# PT_2016_PB_4lyr_Rev2.net
KiCad netlist of a schematic drawn in EAGLE
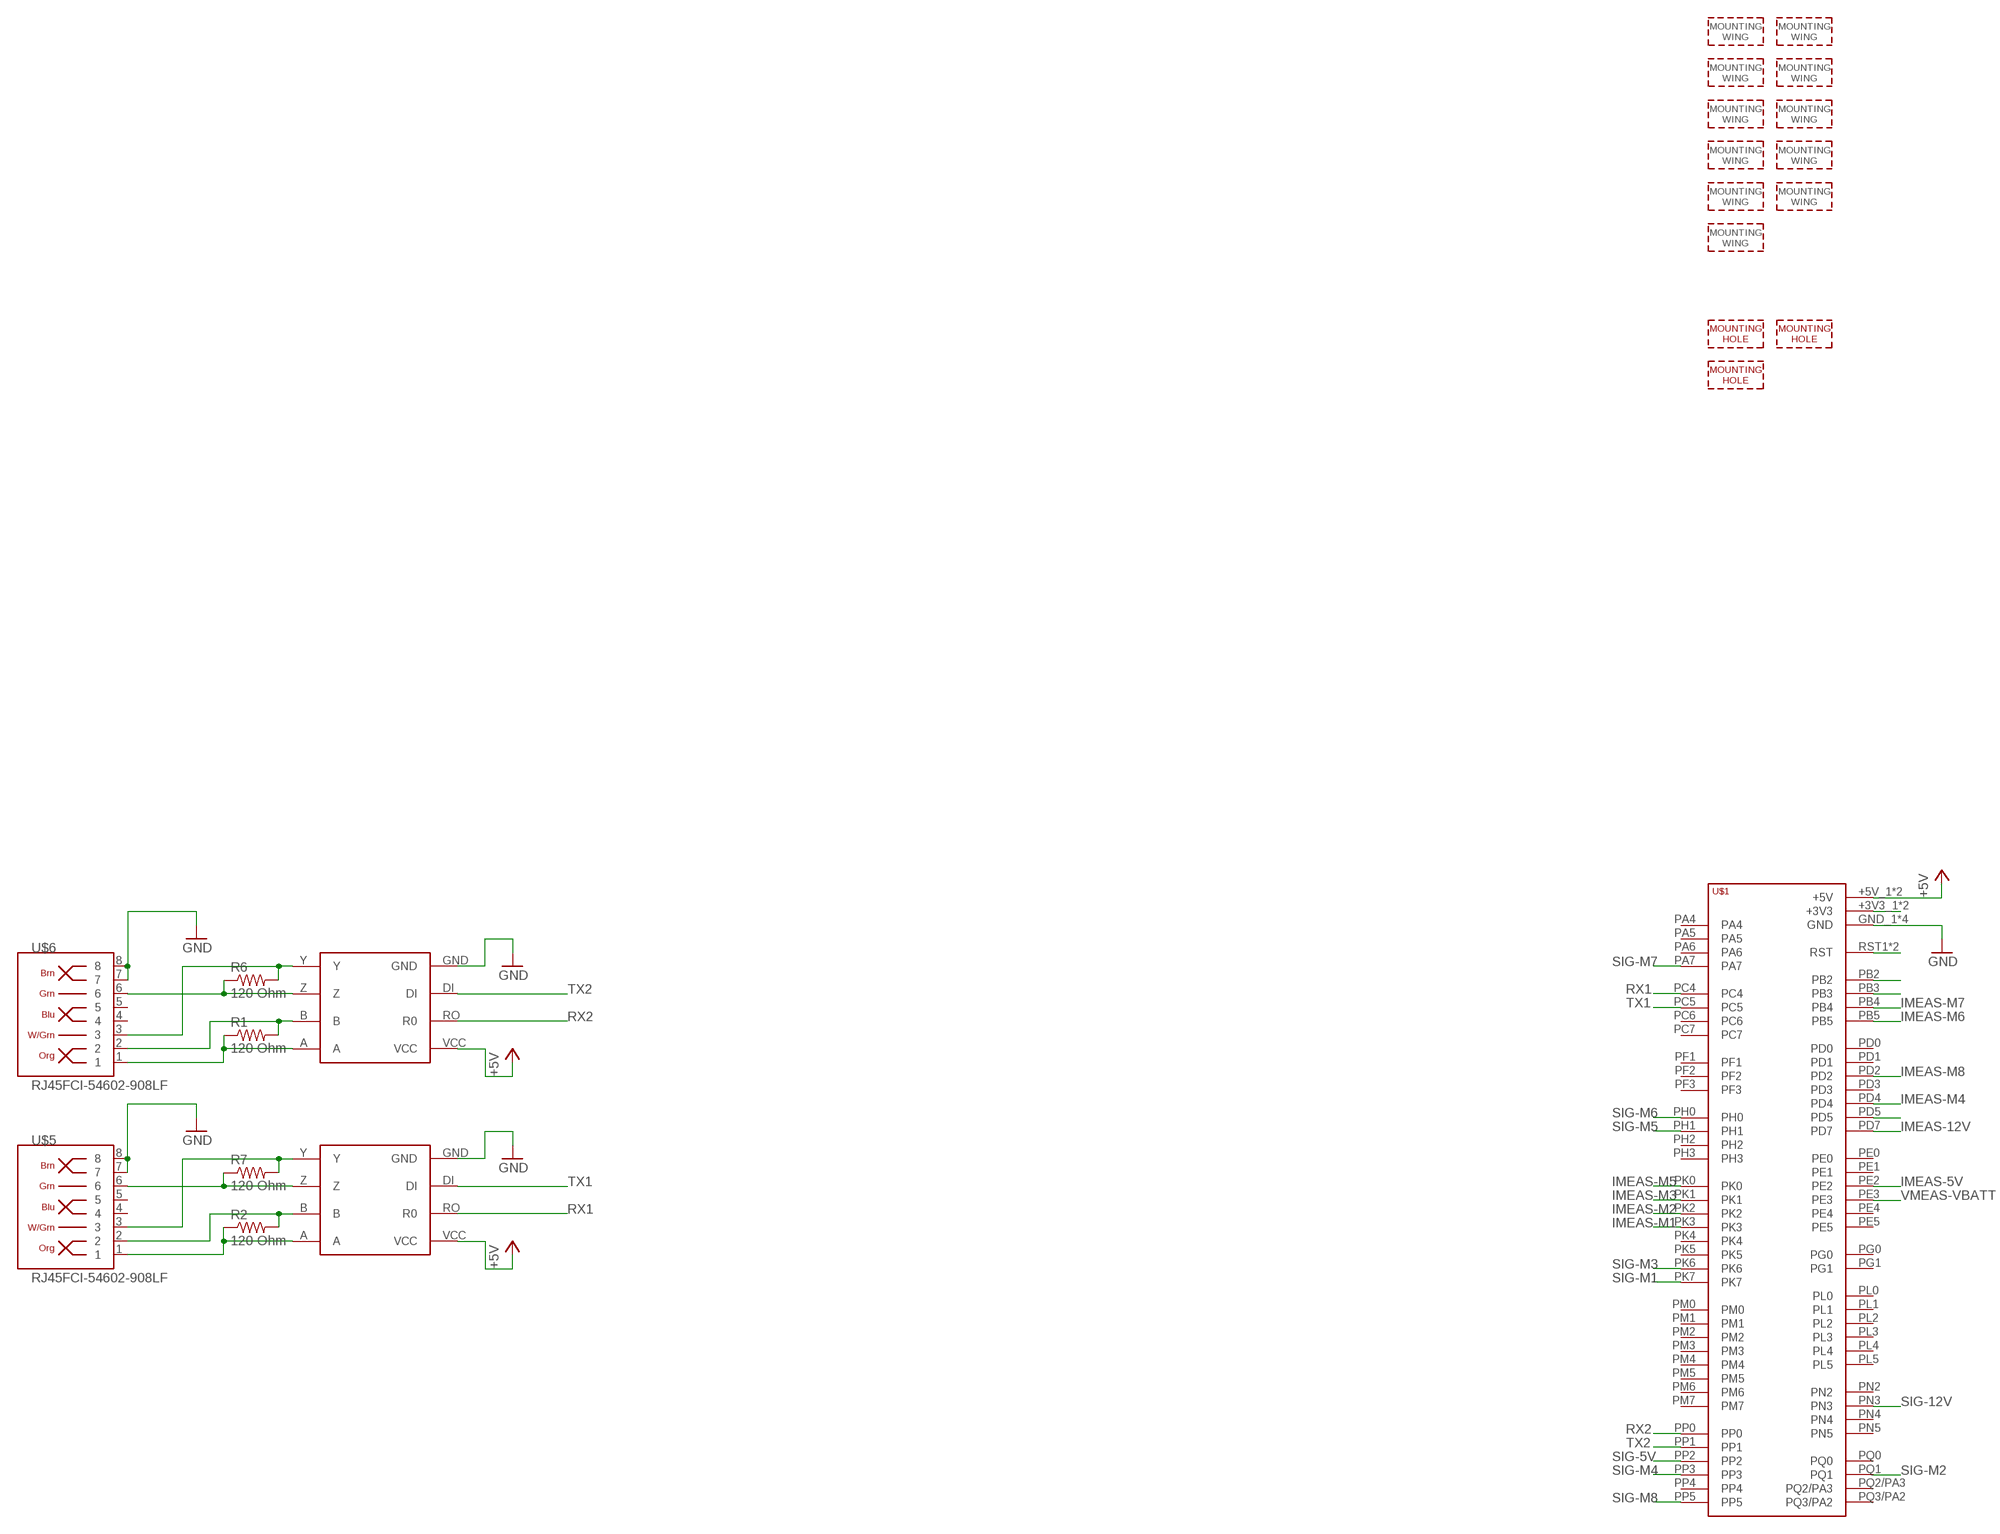
[diagram p0: schematic, sheet 1, part 1 of 3]
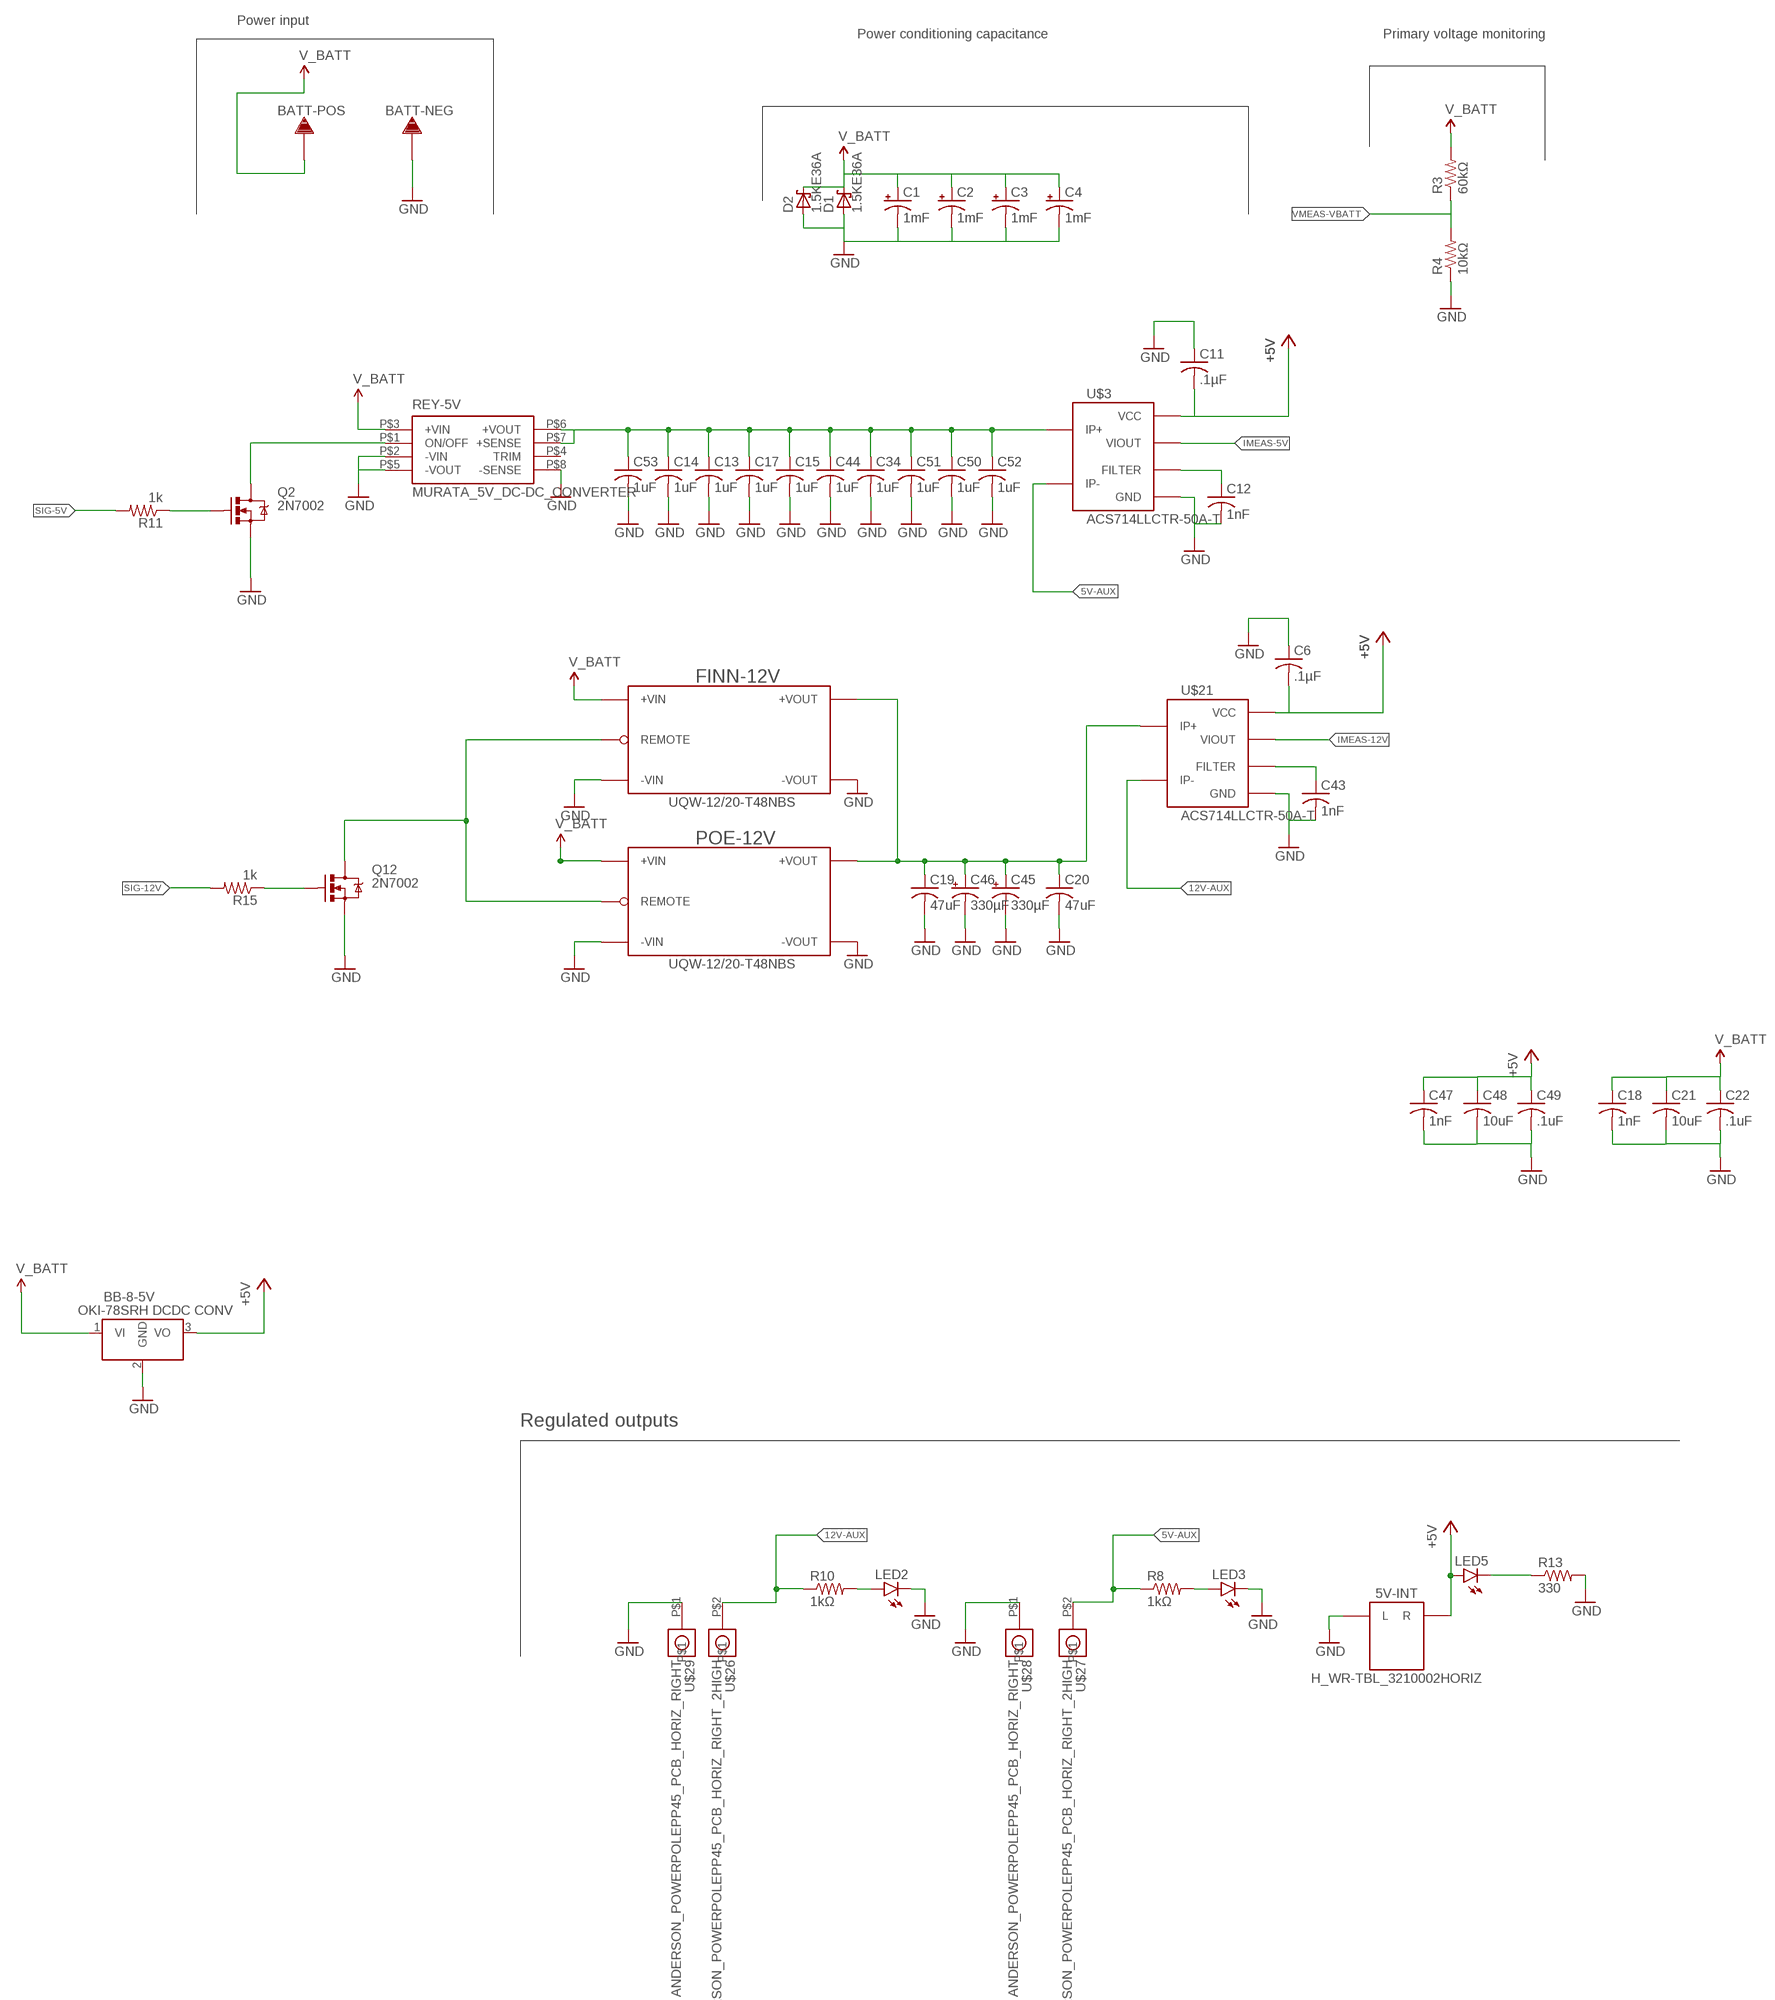
[diagram p1: schematic, sheet 1, part 2 of 3]
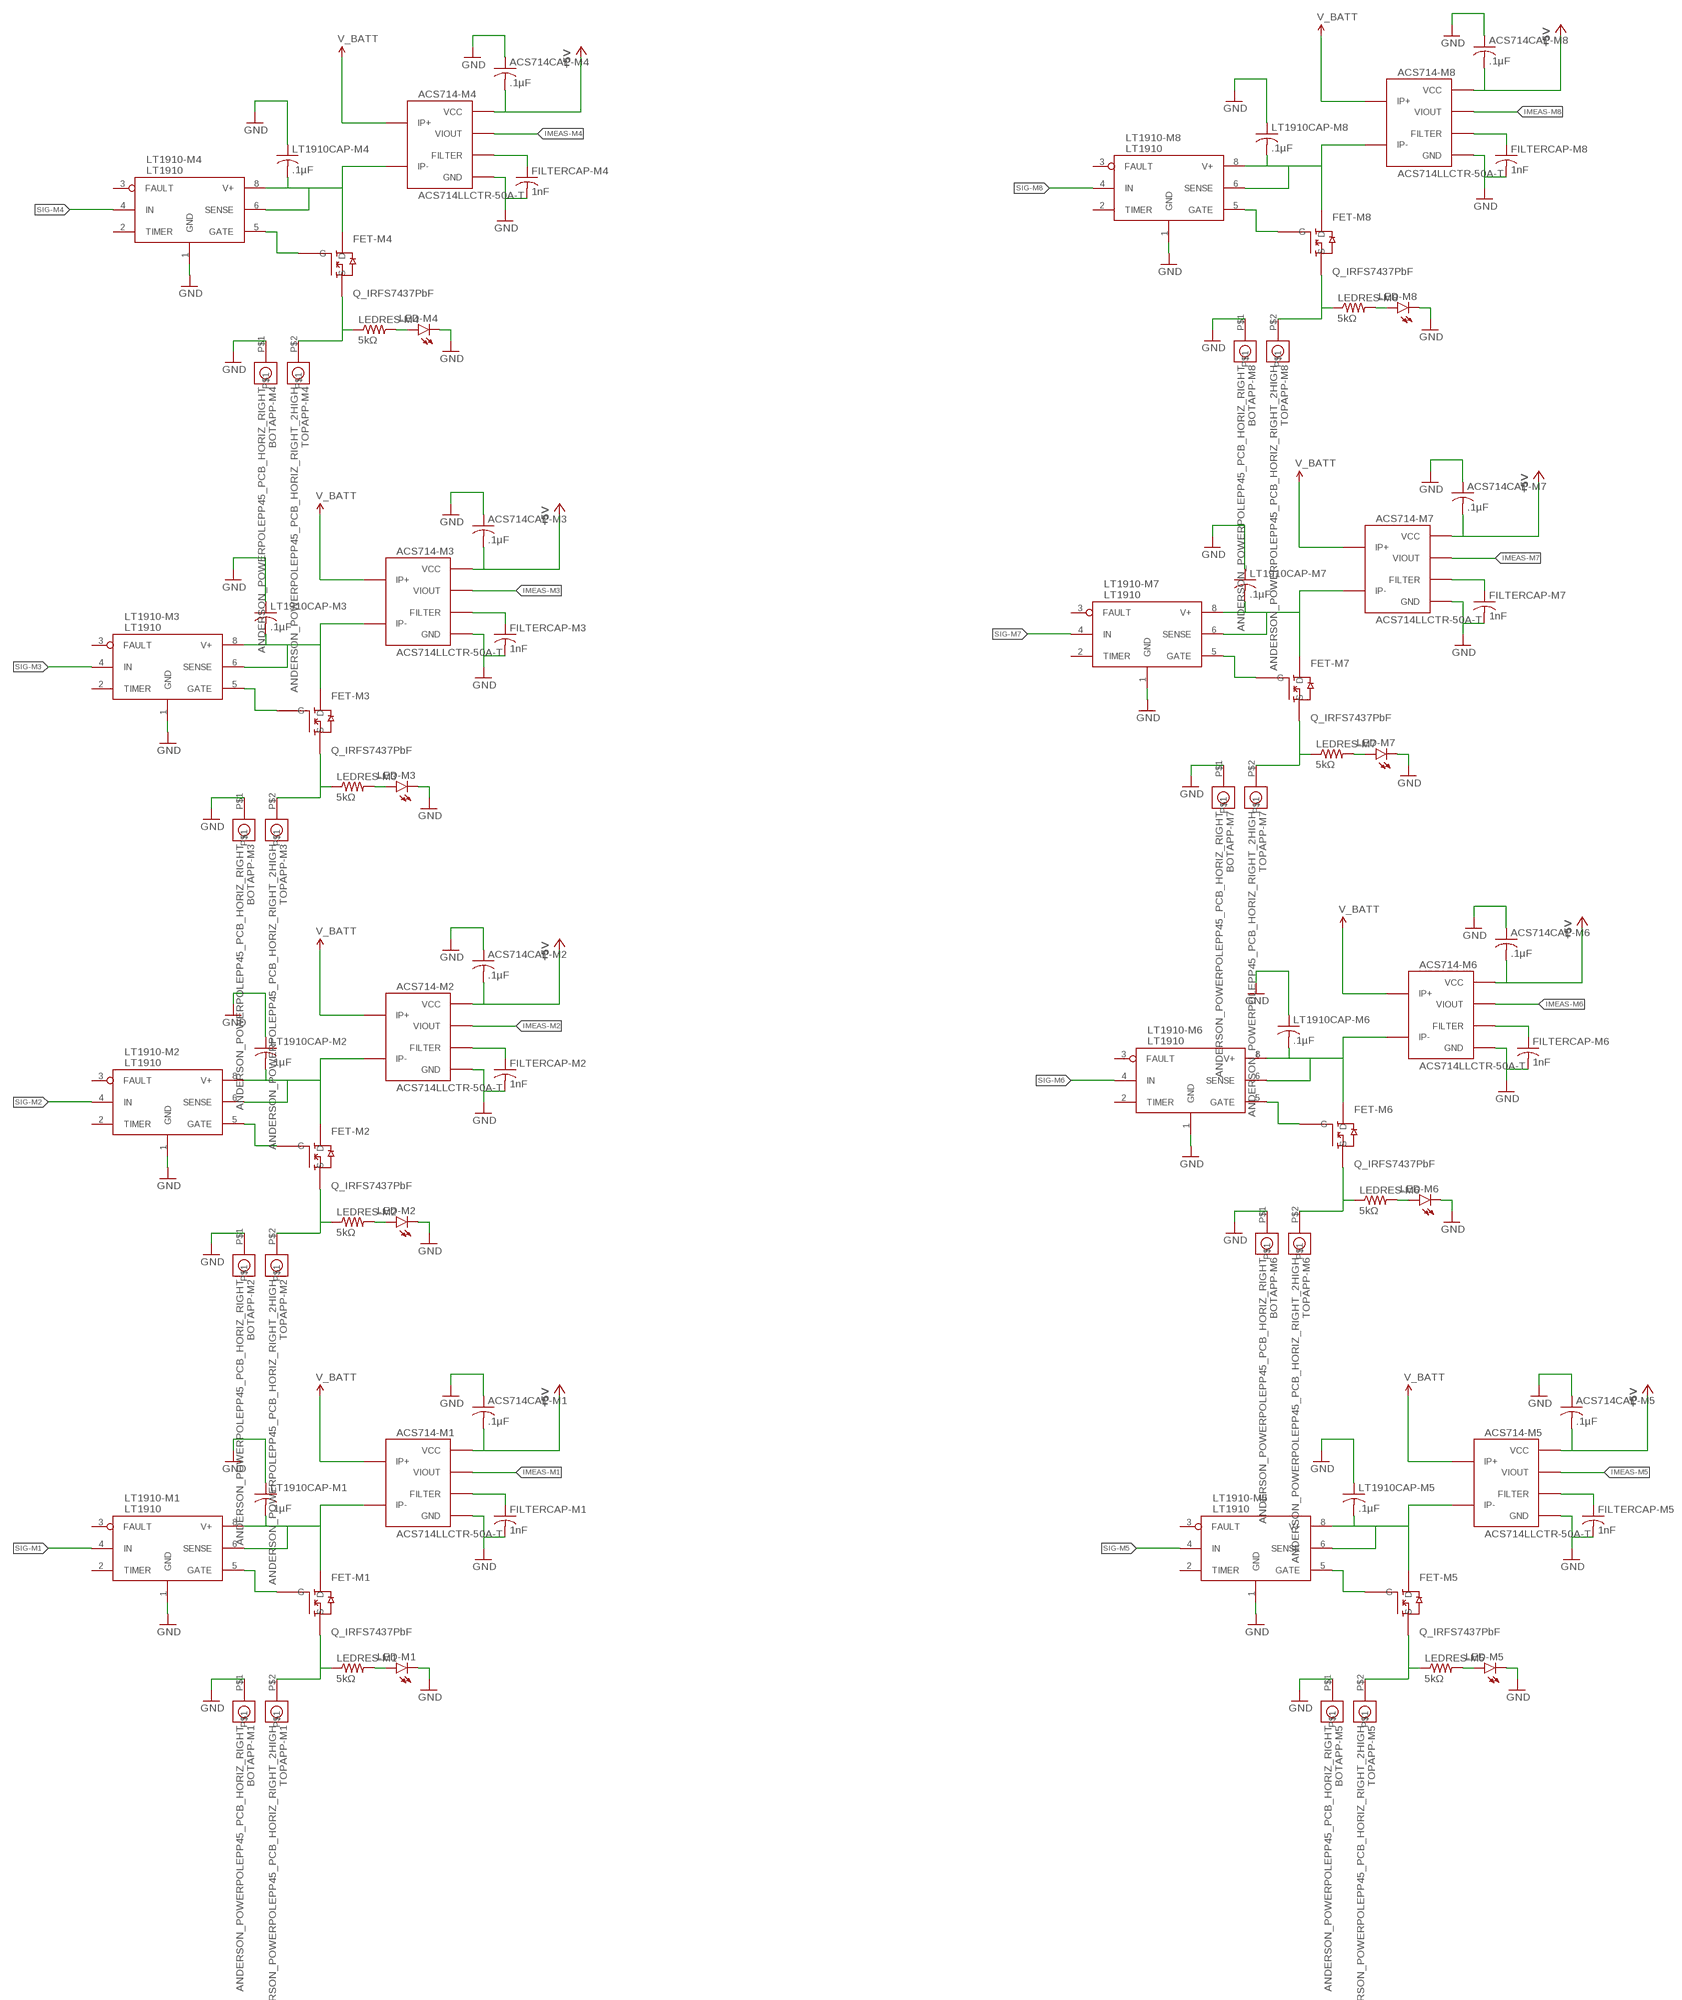
[diagram p2: schematic, sheet 1, part 3 of 3]

(export (version "E")
  (design (tool "Eeschema 10.0.6"))
  (components
    (comp (ref "5V-INT")
      (value "H_WR-TBL_3210002HORIZ")
      (footprint "eagle-import:691322110002")
      (libsource (lib "eagle-import") (part "H_WR-TBL_3210002HORIZ"))
    )
    (comp (ref "ACS714-M1")
      (value "ACS714LLCTR-50A-T")
      (footprint "eagle-import:SOIC8_ACS711")
      (libsource (lib "eagle-import") (part "Q_ACS714"))
    )
    (comp (ref "ACS714-M2")
      (value "ACS714LLCTR-50A-T")
      (footprint "eagle-import:SOIC8_ACS711")
      (libsource (lib "eagle-import") (part "Q_ACS714"))
    )
    (comp (ref "ACS714-M3")
      (value "ACS714LLCTR-50A-T")
      (footprint "eagle-import:SOIC8_ACS711")
      (libsource (lib "eagle-import") (part "Q_ACS714"))
    )
    (comp (ref "ACS714-M4")
      (value "ACS714LLCTR-50A-T")
      (footprint "eagle-import:SOIC8_ACS711")
      (libsource (lib "eagle-import") (part "Q_ACS714"))
    )
    (comp (ref "ACS714-M5")
      (value "ACS714LLCTR-50A-T")
      (footprint "eagle-import:SOIC8_ACS711")
      (libsource (lib "eagle-import") (part "Q_ACS714"))
    )
    (comp (ref "ACS714-M6")
      (value "ACS714LLCTR-50A-T")
      (footprint "eagle-import:SOIC8_ACS711")
      (libsource (lib "eagle-import") (part "Q_ACS714"))
    )
    (comp (ref "ACS714-M7")
      (value "ACS714LLCTR-50A-T")
      (footprint "eagle-import:SOIC8_ACS711")
      (libsource (lib "eagle-import") (part "Q_ACS714"))
    )
    (comp (ref "ACS714-M8")
      (value "ACS714LLCTR-50A-T")
      (footprint "eagle-import:SOIC8_ACS711")
      (libsource (lib "eagle-import") (part "Q_ACS714"))
    )
    (comp (ref "ACS714CAP-M1")
      (value ".1µF")
      (footprint "eagle-import:C1206")
      (libsource (lib "eagle-import") (part "C-USC1206"))
    )
    (comp (ref "ACS714CAP-M2")
      (value ".1µF")
      (footprint "eagle-import:C1206")
      (libsource (lib "eagle-import") (part "C-USC1206"))
    )
    (comp (ref "ACS714CAP-M3")
      (value ".1µF")
      (footprint "eagle-import:C1206")
      (libsource (lib "eagle-import") (part "C-USC1206"))
    )
    (comp (ref "ACS714CAP-M4")
      (value ".1µF")
      (footprint "eagle-import:C1206")
      (libsource (lib "eagle-import") (part "C-USC1206"))
    )
    (comp (ref "ACS714CAP-M5")
      (value ".1µF")
      (footprint "eagle-import:C1206")
      (libsource (lib "eagle-import") (part "C-USC1206"))
    )
    (comp (ref "ACS714CAP-M6")
      (value ".1µF")
      (footprint "eagle-import:C1206")
      (libsource (lib "eagle-import") (part "C-USC1206"))
    )
    (comp (ref "ACS714CAP-M7")
      (value ".1µF")
      (footprint "eagle-import:C1206")
      (libsource (lib "eagle-import") (part "C-USC1206"))
    )
    (comp (ref "ACS714CAP-M8")
      (value ".1µF")
      (footprint "eagle-import:C1206")
      (libsource (lib "eagle-import") (part "C-USC1206"))
    )
    (comp (ref "BATT-NEG")
      (value "TERMINAL_HOLE")
      (footprint "eagle-import:LARGE_TERMINAL_HOLE")
      (libsource (lib "eagle-import") (part "TERMINAL_HOLE"))
    )
    (comp (ref "BATT-POS")
      (value "TERMINAL_HOLE")
      (footprint "eagle-import:LARGE_TERMINAL_HOLE")
      (libsource (lib "eagle-import") (part "TERMINAL_HOLE"))
    )
    (comp (ref "BB-8-5V")
      (value "Q_OKI-78SR")
      (footprint "eagle-import:OKI-78SRH")
      (libsource (lib "eagle-import") (part "Q_OKI-78SR"))
    )
    (comp (ref "BOTAPP-M1")
      (value "ANDERSON_POWERPOLEPP45_PCB_HORIZ_RIGHT")
      (footprint "eagle-import:APP45_PCB_HORIZ_RIGHT")
      (libsource (lib "eagle-import") (part "ANDERSON_POWERPOLEPP45_PCB_HORIZ_RIGHT"))
    )
    (comp (ref "BOTAPP-M2")
      (value "ANDERSON_POWERPOLEPP45_PCB_HORIZ_RIGHT")
      (footprint "eagle-import:APP45_PCB_HORIZ_RIGHT")
      (libsource (lib "eagle-import") (part "ANDERSON_POWERPOLEPP45_PCB_HORIZ_RIGHT"))
    )
    (comp (ref "BOTAPP-M3")
      (value "ANDERSON_POWERPOLEPP45_PCB_HORIZ_RIGHT")
      (footprint "eagle-import:APP45_PCB_HORIZ_RIGHT")
      (libsource (lib "eagle-import") (part "ANDERSON_POWERPOLEPP45_PCB_HORIZ_RIGHT"))
    )
    (comp (ref "BOTAPP-M4")
      (value "ANDERSON_POWERPOLEPP45_PCB_HORIZ_RIGHT")
      (footprint "eagle-import:APP45_PCB_HORIZ_RIGHT")
      (libsource (lib "eagle-import") (part "ANDERSON_POWERPOLEPP45_PCB_HORIZ_RIGHT"))
    )
    (comp (ref "BOTAPP-M5")
      (value "ANDERSON_POWERPOLEPP45_PCB_HORIZ_RIGHT")
      (footprint "eagle-import:APP45_PCB_HORIZ_RIGHT")
      (libsource (lib "eagle-import") (part "ANDERSON_POWERPOLEPP45_PCB_HORIZ_RIGHT"))
    )
    (comp (ref "BOTAPP-M6")
      (value "ANDERSON_POWERPOLEPP45_PCB_HORIZ_RIGHT")
      (footprint "eagle-import:APP45_PCB_HORIZ_RIGHT")
      (libsource (lib "eagle-import") (part "ANDERSON_POWERPOLEPP45_PCB_HORIZ_RIGHT"))
    )
    (comp (ref "BOTAPP-M7")
      (value "ANDERSON_POWERPOLEPP45_PCB_HORIZ_RIGHT")
      (footprint "eagle-import:APP45_PCB_HORIZ_RIGHT")
      (libsource (lib "eagle-import") (part "ANDERSON_POWERPOLEPP45_PCB_HORIZ_RIGHT"))
    )
    (comp (ref "BOTAPP-M8")
      (value "ANDERSON_POWERPOLEPP45_PCB_HORIZ_RIGHT")
      (footprint "eagle-import:APP45_PCB_HORIZ_RIGHT")
      (libsource (lib "eagle-import") (part "ANDERSON_POWERPOLEPP45_PCB_HORIZ_RIGHT"))
    )
    (comp (ref "C1")
      (value "1mF")
      (footprint "eagle-import:C_12.5MM")
      (libsource (lib "eagle-import") (part "C_POL12.5MM_NORMAL"))
    )
    (comp (ref "C2")
      (value "1mF")
      (footprint "eagle-import:C_12.5MM")
      (libsource (lib "eagle-import") (part "C_POL12.5MM_NORMAL"))
    )
    (comp (ref "C3")
      (value "1mF")
      (footprint "eagle-import:C_12.5MM")
      (libsource (lib "eagle-import") (part "C_POL12.5MM_NORMAL"))
    )
    (comp (ref "C4")
      (value "1mF")
      (footprint "eagle-import:C_12.5MM")
      (libsource (lib "eagle-import") (part "C_POL12.5MM_NORMAL"))
    )
    (comp (ref "C6")
      (value ".1µF")
      (footprint "eagle-import:C1206")
      (libsource (lib "eagle-import") (part "C-USC1206"))
    )
    (comp (ref "C11")
      (value ".1µF")
      (footprint "eagle-import:C1206")
      (libsource (lib "eagle-import") (part "C-USC1206"))
    )
    (comp (ref "C12")
      (value "1nF")
      (footprint "eagle-import:C1206")
      (libsource (lib "eagle-import") (part "C-USC1206"))
    )
    (comp (ref "C13")
      (value "1uF")
      (footprint "eagle-import:C1206")
      (libsource (lib "eagle-import") (part "C-USC1206"))
    )
    (comp (ref "C14")
      (value "1uF")
      (footprint "eagle-import:C1206")
      (libsource (lib "eagle-import") (part "C-USC1206"))
    )
    (comp (ref "C15")
      (value "1uF")
      (footprint "eagle-import:C1206")
      (libsource (lib "eagle-import") (part "C-USC1206"))
    )
    (comp (ref "C17")
      (value "1uF")
      (footprint "eagle-import:C1206")
      (libsource (lib "eagle-import") (part "C-USC1206"))
    )
    (comp (ref "C18")
      (value "1nF")
      (footprint "eagle-import:C1206")
      (libsource (lib "eagle-import") (part "C-USC1206"))
    )
    (comp (ref "C19")
      (value "47uF")
      (footprint "eagle-import:C1206")
      (libsource (lib "eagle-import") (part "C-USC1206"))
    )
    (comp (ref "C20")
      (value "47uF")
      (footprint "eagle-import:C1206")
      (libsource (lib "eagle-import") (part "C-USC1206"))
    )
    (comp (ref "C21")
      (value "10uF")
      (footprint "eagle-import:C1206")
      (libsource (lib "eagle-import") (part "C-USC1206"))
    )
    (comp (ref "C22")
      (value ".1uF")
      (footprint "eagle-import:C1206")
      (libsource (lib "eagle-import") (part "C-USC1206"))
    )
    (comp (ref "C34")
      (value "1uF")
      (footprint "eagle-import:C1206")
      (libsource (lib "eagle-import") (part "C-USC1206"))
    )
    (comp (ref "C43")
      (value "1nF")
      (footprint "eagle-import:C1206")
      (libsource (lib "eagle-import") (part "C-USC1206"))
    )
    (comp (ref "C44")
      (value "1uF")
      (footprint "eagle-import:C1206")
      (libsource (lib "eagle-import") (part "C-USC1206"))
    )
    (comp (ref "C45")
      (value "330µF")
      (footprint "eagle-import:E5-8,5")
      (libsource (lib "eagle-import") (part "CPOL-USE5-8.5"))
    )
    (comp (ref "C46")
      (value "330µF")
      (footprint "eagle-import:E5-8,5")
      (libsource (lib "eagle-import") (part "CPOL-USE5-8.5"))
    )
    (comp (ref "C47")
      (value "1nF")
      (footprint "eagle-import:C1206")
      (libsource (lib "eagle-import") (part "C-USC1206"))
    )
    (comp (ref "C48")
      (value "10uF")
      (footprint "eagle-import:C1206")
      (libsource (lib "eagle-import") (part "C-USC1206"))
    )
    (comp (ref "C49")
      (value ".1uF")
      (footprint "eagle-import:C1206")
      (libsource (lib "eagle-import") (part "C-USC1206"))
    )
    (comp (ref "C50")
      (value "1uF")
      (footprint "eagle-import:C1206")
      (libsource (lib "eagle-import") (part "C-USC1206"))
    )
    (comp (ref "C51")
      (value "1uF")
      (footprint "eagle-import:C1206")
      (libsource (lib "eagle-import") (part "C-USC1206"))
    )
    (comp (ref "C52")
      (value "1uF")
      (footprint "eagle-import:C1206")
      (libsource (lib "eagle-import") (part "C-USC1206"))
    )
    (comp (ref "C53")
      (value "1uF")
      (footprint "eagle-import:C1206")
      (libsource (lib "eagle-import") (part "C-USC1206"))
    )
    (comp (ref "D1")
      (value "1.5KE36A")
      (footprint "eagle-import:CB429-17")
      (libsource (lib "eagle-import") (part "15KEXX"))
    )
    (comp (ref "D2")
      (value "1.5KE36A")
      (footprint "eagle-import:CB429-17")
      (libsource (lib "eagle-import") (part "15KEXX"))
    )
    (comp (ref "FET-M1")
      (value "Q_IRFS7437PbF")
      (footprint "eagle-import:D2PACK")
      (libsource (lib "eagle-import") (part "Q_IRF7437SMD"))
    )
    (comp (ref "FET-M2")
      (value "Q_IRFS7437PbF")
      (footprint "eagle-import:D2PACK")
      (libsource (lib "eagle-import") (part "Q_IRF7437SMD"))
    )
    (comp (ref "FET-M3")
      (value "Q_IRFS7437PbF")
      (footprint "eagle-import:D2PACK")
      (libsource (lib "eagle-import") (part "Q_IRF7437SMD"))
    )
    (comp (ref "FET-M4")
      (value "Q_IRFS7437PbF")
      (footprint "eagle-import:D2PACK")
      (libsource (lib "eagle-import") (part "Q_IRF7437SMD"))
    )
    (comp (ref "FET-M5")
      (value "Q_IRFS7437PbF")
      (footprint "eagle-import:D2PACK")
      (libsource (lib "eagle-import") (part "Q_IRF7437SMD"))
    )
    (comp (ref "FET-M6")
      (value "Q_IRFS7437PbF")
      (footprint "eagle-import:D2PACK")
      (libsource (lib "eagle-import") (part "Q_IRF7437SMD"))
    )
    (comp (ref "FET-M7")
      (value "Q_IRFS7437PbF")
      (footprint "eagle-import:D2PACK")
      (libsource (lib "eagle-import") (part "Q_IRF7437SMD"))
    )
    (comp (ref "FET-M8")
      (value "Q_IRFS7437PbF")
      (footprint "eagle-import:D2PACK")
      (libsource (lib "eagle-import") (part "Q_IRF7437SMD"))
    )
    (comp (ref "FILTERCAP-M1")
      (value "1nF")
      (footprint "eagle-import:C1206")
      (libsource (lib "eagle-import") (part "C-USC1206"))
    )
    (comp (ref "FILTERCAP-M2")
      (value "1nF")
      (footprint "eagle-import:C1206")
      (libsource (lib "eagle-import") (part "C-USC1206"))
    )
    (comp (ref "FILTERCAP-M3")
      (value "1nF")
      (footprint "eagle-import:C1206")
      (libsource (lib "eagle-import") (part "C-USC1206"))
    )
    (comp (ref "FILTERCAP-M4")
      (value "1nF")
      (footprint "eagle-import:C1206")
      (libsource (lib "eagle-import") (part "C-USC1206"))
    )
    (comp (ref "FILTERCAP-M5")
      (value "1nF")
      (footprint "eagle-import:C1206")
      (libsource (lib "eagle-import") (part "C-USC1206"))
    )
    (comp (ref "FILTERCAP-M6")
      (value "1nF")
      (footprint "eagle-import:C1206")
      (libsource (lib "eagle-import") (part "C-USC1206"))
    )
    (comp (ref "FILTERCAP-M7")
      (value "1nF")
      (footprint "eagle-import:C1206")
      (libsource (lib "eagle-import") (part "C-USC1206"))
    )
    (comp (ref "FILTERCAP-M8")
      (value "1nF")
      (footprint "eagle-import:C1206")
      (libsource (lib "eagle-import") (part "C-USC1206"))
    )
    (comp (ref "FINN-12V")
      (value "UQW-12/20-T48NBS")
      (footprint "eagle-import:U-T48-QB-NO_TRIM")
      (libsource (lib "eagle-import") (part "UQW-12/20-T48NBS"))
    )
    (comp (ref "LED-M1")
      (value "LED1206")
      (footprint "eagle-import:LED-1206")
      (libsource (lib "eagle-import") (part "LED1206"))
    )
    (comp (ref "LED-M2")
      (value "LED1206")
      (footprint "eagle-import:LED-1206")
      (libsource (lib "eagle-import") (part "LED1206"))
    )
    (comp (ref "LED-M3")
      (value "LED1206")
      (footprint "eagle-import:LED-1206")
      (libsource (lib "eagle-import") (part "LED1206"))
    )
    (comp (ref "LED-M4")
      (value "LED1206")
      (footprint "eagle-import:LED-1206")
      (libsource (lib "eagle-import") (part "LED1206"))
    )
    (comp (ref "LED-M5")
      (value "LED1206")
      (footprint "eagle-import:LED-1206")
      (libsource (lib "eagle-import") (part "LED1206"))
    )
    (comp (ref "LED-M6")
      (value "LED1206")
      (footprint "eagle-import:LED-1206")
      (libsource (lib "eagle-import") (part "LED1206"))
    )
    (comp (ref "LED-M7")
      (value "LED1206")
      (footprint "eagle-import:LED-1206")
      (libsource (lib "eagle-import") (part "LED1206"))
    )
    (comp (ref "LED-M8")
      (value "LED1206")
      (footprint "eagle-import:LED-1206")
      (libsource (lib "eagle-import") (part "LED1206"))
    )
    (comp (ref "LED2")
      (value "LED1206")
      (footprint "eagle-import:LED-1206")
      (libsource (lib "eagle-import") (part "LED1206"))
    )
    (comp (ref "LED3")
      (value "LED1206")
      (footprint "eagle-import:LED-1206")
      (libsource (lib "eagle-import") (part "LED1206"))
    )
    (comp (ref "LED5")
      (value "LED1206")
      (footprint "eagle-import:LED-1206")
      (libsource (lib "eagle-import") (part "LED1206"))
    )
    (comp (ref "LEDRES-M1")
      (value "5kΩ")
      (footprint "eagle-import:1206")
      (libsource (lib "eagle-import") (part "RESISTOR1206"))
    )
    (comp (ref "LEDRES-M2")
      (value "5kΩ")
      (footprint "eagle-import:1206")
      (libsource (lib "eagle-import") (part "RESISTOR1206"))
    )
    (comp (ref "LEDRES-M3")
      (value "5kΩ")
      (footprint "eagle-import:1206")
      (libsource (lib "eagle-import") (part "RESISTOR1206"))
    )
    (comp (ref "LEDRES-M4")
      (value "5kΩ")
      (footprint "eagle-import:1206")
      (libsource (lib "eagle-import") (part "RESISTOR1206"))
    )
    (comp (ref "LEDRES-M5")
      (value "5kΩ")
      (footprint "eagle-import:1206")
      (libsource (lib "eagle-import") (part "RESISTOR1206"))
    )
    (comp (ref "LEDRES-M6")
      (value "5kΩ")
      (footprint "eagle-import:1206")
      (libsource (lib "eagle-import") (part "RESISTOR1206"))
    )
    (comp (ref "LEDRES-M7")
      (value "5kΩ")
      (footprint "eagle-import:1206")
      (libsource (lib "eagle-import") (part "RESISTOR1206"))
    )
    (comp (ref "LEDRES-M8")
      (value "5kΩ")
      (footprint "eagle-import:1206")
      (libsource (lib "eagle-import") (part "RESISTOR1206"))
    )
    (comp (ref "LT1910-M1")
      (value "LT1910")
      (footprint "eagle-import:SO8")
      (libsource (lib "eagle-import") (part "LT1910"))
    )
    (comp (ref "LT1910-M2")
      (value "LT1910")
      (footprint "eagle-import:SO8")
      (libsource (lib "eagle-import") (part "LT1910"))
    )
    (comp (ref "LT1910-M3")
      (value "LT1910")
      (footprint "eagle-import:SO8")
      (libsource (lib "eagle-import") (part "LT1910"))
    )
    (comp (ref "LT1910-M4")
      (value "LT1910")
      (footprint "eagle-import:SO8")
      (libsource (lib "eagle-import") (part "LT1910"))
    )
    (comp (ref "LT1910-M5")
      (value "LT1910")
      (footprint "eagle-import:SO8")
      (libsource (lib "eagle-import") (part "LT1910"))
    )
    (comp (ref "LT1910-M6")
      (value "LT1910")
      (footprint "eagle-import:SO8")
      (libsource (lib "eagle-import") (part "LT1910"))
    )
    (comp (ref "LT1910-M7")
      (value "LT1910")
      (footprint "eagle-import:SO8")
      (libsource (lib "eagle-import") (part "LT1910"))
    )
    (comp (ref "LT1910-M8")
      (value "LT1910")
      (footprint "eagle-import:SO8")
      (libsource (lib "eagle-import") (part "LT1910"))
    )
    (comp (ref "LT1910CAP-M1")
      (value ".1µF")
      (footprint "eagle-import:C1206")
      (libsource (lib "eagle-import") (part "C-USC1206"))
    )
    (comp (ref "LT1910CAP-M2")
      (value ".1µF")
      (footprint "eagle-import:C1206")
      (libsource (lib "eagle-import") (part "C-USC1206"))
    )
    (comp (ref "LT1910CAP-M3")
      (value ".1µF")
      (footprint "eagle-import:C1206")
      (libsource (lib "eagle-import") (part "C-USC1206"))
    )
    (comp (ref "LT1910CAP-M4")
      (value ".1µF")
      (footprint "eagle-import:C1206")
      (libsource (lib "eagle-import") (part "C-USC1206"))
    )
    (comp (ref "LT1910CAP-M5")
      (value ".1µF")
      (footprint "eagle-import:C1206")
      (libsource (lib "eagle-import") (part "C-USC1206"))
    )
    (comp (ref "LT1910CAP-M6")
      (value ".1µF")
      (footprint "eagle-import:C1206")
      (libsource (lib "eagle-import") (part "C-USC1206"))
    )
    (comp (ref "LT1910CAP-M7")
      (value ".1µF")
      (footprint "eagle-import:C1206")
      (libsource (lib "eagle-import") (part "C-USC1206"))
    )
    (comp (ref "LT1910CAP-M8")
      (value ".1µF")
      (footprint "eagle-import:C1206")
      (libsource (lib "eagle-import") (part "C-USC1206"))
    )
    (comp (ref "POE-12V")
      (value "UQW-12/20-T48NBS")
      (footprint "eagle-import:U-T48-QB-NO_TRIM")
      (libsource (lib "eagle-import") (part "UQW-12/20-T48NBS"))
    )
    (comp (ref "Q2")
      (value "2N7002")
      (footprint "eagle-import:SOT323")
      (libsource (lib "eagle-import") (part "MOSFET-NCHANNEL2N7002PW"))
    )
    (comp (ref "Q12")
      (value "2N7002")
      (footprint "eagle-import:SOT323")
      (libsource (lib "eagle-import") (part "MOSFET-NCHANNEL2N7002PW"))
    )
    (comp (ref "R1")
      (value "120 Ohm")
      (footprint "eagle-import:1206")
      (libsource (lib "eagle-import") (part "RESISTOR1206"))
    )
    (comp (ref "R2")
      (value "120 Ohm")
      (footprint "eagle-import:1206")
      (libsource (lib "eagle-import") (part "RESISTOR1206"))
    )
    (comp (ref "R3")
      (value "60kΩ")
      (footprint "eagle-import:R1206")
      (libsource (lib "eagle-import") (part "R-US_R1206"))
    )
    (comp (ref "R4")
      (value "10kΩ")
      (footprint "eagle-import:R1206")
      (libsource (lib "eagle-import") (part "R-US_R1206"))
    )
    (comp (ref "R6")
      (value "120 Ohm")
      (footprint "eagle-import:1206")
      (libsource (lib "eagle-import") (part "RESISTOR1206"))
    )
    (comp (ref "R7")
      (value "120 Ohm")
      (footprint "eagle-import:1206")
      (libsource (lib "eagle-import") (part "RESISTOR1206"))
    )
    (comp (ref "R8")
      (value "1kΩ")
      (footprint "eagle-import:1206")
      (libsource (lib "eagle-import") (part "RESISTOR1206"))
    )
    (comp (ref "R10")
      (value "1kΩ")
      (footprint "eagle-import:1206")
      (libsource (lib "eagle-import") (part "RESISTOR1206"))
    )
    (comp (ref "R11")
      (value "1k")
      (footprint "eagle-import:R1206")
      (libsource (lib "eagle-import") (part "R-US_R1206"))
    )
    (comp (ref "R13")
      (value "330")
      (footprint "eagle-import:1206")
      (libsource (lib "eagle-import") (part "RESISTOR1206"))
    )
    (comp (ref "R15")
      (value "1k")
      (footprint "eagle-import:R1206")
      (libsource (lib "eagle-import") (part "R-US_R1206"))
    )
    (comp (ref "REY-5V")
      (value "MURATA_5V_DC-DC_CONVERTER")
      (footprint "eagle-import:MURATA_5V_DC-DC_CONVERTER")
      (libsource (lib "eagle-import") (part "MURATA_5V_DC-DC_CONVERTER"))
    )
    (comp (ref "TOPAPP-M1")
      (value "ANDERSON_POWERPOLEPP45_PCB_HORIZ_RIGHT_2HIGH")
      (footprint "eagle-import:APP45_PCB_HORIZ_RIGHT_2HIGH")
      (libsource (lib "eagle-import") (part "ANDERSON_POWERPOLEPP45_PCB_HORIZ_RIGHT_2HIGH"))
    )
    (comp (ref "TOPAPP-M2")
      (value "ANDERSON_POWERPOLEPP45_PCB_HORIZ_RIGHT_2HIGH")
      (footprint "eagle-import:APP45_PCB_HORIZ_RIGHT_2HIGH")
      (libsource (lib "eagle-import") (part "ANDERSON_POWERPOLEPP45_PCB_HORIZ_RIGHT_2HIGH"))
    )
    (comp (ref "TOPAPP-M3")
      (value "ANDERSON_POWERPOLEPP45_PCB_HORIZ_RIGHT_2HIGH")
      (footprint "eagle-import:APP45_PCB_HORIZ_RIGHT_2HIGH")
      (libsource (lib "eagle-import") (part "ANDERSON_POWERPOLEPP45_PCB_HORIZ_RIGHT_2HIGH"))
    )
    (comp (ref "TOPAPP-M4")
      (value "ANDERSON_POWERPOLEPP45_PCB_HORIZ_RIGHT_2HIGH")
      (footprint "eagle-import:APP45_PCB_HORIZ_RIGHT_2HIGH")
      (libsource (lib "eagle-import") (part "ANDERSON_POWERPOLEPP45_PCB_HORIZ_RIGHT_2HIGH"))
    )
    (comp (ref "TOPAPP-M5")
      (value "ANDERSON_POWERPOLEPP45_PCB_HORIZ_RIGHT_2HIGH")
      (footprint "eagle-import:APP45_PCB_HORIZ_RIGHT_2HIGH")
      (libsource (lib "eagle-import") (part "ANDERSON_POWERPOLEPP45_PCB_HORIZ_RIGHT_2HIGH"))
    )
    (comp (ref "TOPAPP-M6")
      (value "ANDERSON_POWERPOLEPP45_PCB_HORIZ_RIGHT_2HIGH")
      (footprint "eagle-import:APP45_PCB_HORIZ_RIGHT_2HIGH")
      (libsource (lib "eagle-import") (part "ANDERSON_POWERPOLEPP45_PCB_HORIZ_RIGHT_2HIGH"))
    )
    (comp (ref "TOPAPP-M7")
      (value "ANDERSON_POWERPOLEPP45_PCB_HORIZ_RIGHT_2HIGH")
      (footprint "eagle-import:APP45_PCB_HORIZ_RIGHT_2HIGH")
      (libsource (lib "eagle-import") (part "ANDERSON_POWERPOLEPP45_PCB_HORIZ_RIGHT_2HIGH"))
    )
    (comp (ref "TOPAPP-M8")
      (value "ANDERSON_POWERPOLEPP45_PCB_HORIZ_RIGHT_2HIGH")
      (footprint "eagle-import:APP45_PCB_HORIZ_RIGHT_2HIGH")
      (libsource (lib "eagle-import") (part "ANDERSON_POWERPOLEPP45_PCB_HORIZ_RIGHT_2HIGH"))
    )
    (comp (ref "U$1")
      (value "TIVA-C-CONNECTED")
      (footprint "eagle-import:TIVA-C-CONNECTED")
      (libsource (lib "eagle-import") (part "TIVA-C-CONNECTED"))
    )
    (comp (ref "U$2")
      (value "APP_MOUTING_WINGHORIZ")
      (footprint "eagle-import:APP45_MOUNTING_WING_HORIZ")
      (libsource (lib "eagle-import") (part "APP_MOUTING_WINGHORIZ"))
    )
    (comp (ref "U$3")
      (value "ACS714LLCTR-50A-T")
      (footprint "eagle-import:SOIC8_ACS711")
      (libsource (lib "eagle-import") (part "Q_ACS714"))
    )
    (comp (ref "U$4")
      (value "APP_MOUTING_WINGHORIZ")
      (footprint "eagle-import:APP45_MOUNTING_WING_HORIZ")
      (libsource (lib "eagle-import") (part "APP_MOUTING_WINGHORIZ"))
    )
    (comp (ref "U$5")
      (value "RJ45FCI-54602-908LF")
      (footprint "eagle-import:FCI-54602-908LF")
      (libsource (lib "eagle-import") (part "RJ45FCI-54602-908LF"))
    )
    (comp (ref "U$6")
      (value "RJ45FCI-54602-908LF")
      (footprint "eagle-import:FCI-54602-908LF")
      (libsource (lib "eagle-import") (part "RJ45FCI-54602-908LF"))
    )
    (comp (ref "U$8")
      (value "MOUNTING_HOLE#8")
      (footprint "eagle-import:#8_SCREW")
      (libsource (lib "eagle-import") (part "MOUNTING_HOLE#8"))
    )
    (comp (ref "U$10")
      (value "MOUNTING_HOLE#8")
      (footprint "eagle-import:#8_SCREW")
      (libsource (lib "eagle-import") (part "MOUNTING_HOLE#8"))
    )
    (comp (ref "U$11")
      (value "MOUNTING_HOLE#8")
      (footprint "eagle-import:#8_SCREW")
      (libsource (lib "eagle-import") (part "MOUNTING_HOLE#8"))
    )
    (comp (ref "U$12")
      (value "MAX3077")
      (footprint "eagle-import:MAX3070E")
      (libsource (lib "eagle-import") (part "MAX3077"))
    )
    (comp (ref "U$21")
      (value "ACS714LLCTR-50A-T")
      (footprint "eagle-import:SOIC8_ACS711")
      (libsource (lib "eagle-import") (part "Q_ACS714"))
    )
    (comp (ref "U$24")
      (value "MAX3077")
      (footprint "eagle-import:MAX3070E")
      (libsource (lib "eagle-import") (part "MAX3077"))
    )
    (comp (ref "U$25")
      (value "APP_MOUTING_WINGHORIZ")
      (footprint "eagle-import:APP45_MOUNTING_WING_HORIZ")
      (libsource (lib "eagle-import") (part "APP_MOUTING_WINGHORIZ"))
    )
    (comp (ref "U$26")
      (value "ANDERSON_POWERPOLEPP45_PCB_HORIZ_RIGHT_2HIGH")
      (footprint "eagle-import:APP45_PCB_HORIZ_RIGHT_2HIGH")
      (libsource (lib "eagle-import") (part "ANDERSON_POWERPOLEPP45_PCB_HORIZ_RIGHT_2HIGH"))
    )
    (comp (ref "U$27")
      (value "ANDERSON_POWERPOLEPP45_PCB_HORIZ_RIGHT_2HIGH")
      (footprint "eagle-import:APP45_PCB_HORIZ_RIGHT_2HIGH")
      (libsource (lib "eagle-import") (part "ANDERSON_POWERPOLEPP45_PCB_HORIZ_RIGHT_2HIGH"))
    )
    (comp (ref "U$28")
      (value "ANDERSON_POWERPOLEPP45_PCB_HORIZ_RIGHT")
      (footprint "eagle-import:APP45_PCB_HORIZ_RIGHT")
      (libsource (lib "eagle-import") (part "ANDERSON_POWERPOLEPP45_PCB_HORIZ_RIGHT"))
    )
    (comp (ref "U$29")
      (value "ANDERSON_POWERPOLEPP45_PCB_HORIZ_RIGHT")
      (footprint "eagle-import:APP45_PCB_HORIZ_RIGHT")
      (libsource (lib "eagle-import") (part "ANDERSON_POWERPOLEPP45_PCB_HORIZ_RIGHT"))
    )
    (comp (ref "U$30")
      (value "APP_MOUTING_WINGHORIZ")
      (footprint "eagle-import:APP45_MOUNTING_WING_HORIZ")
      (libsource (lib "eagle-import") (part "APP_MOUTING_WINGHORIZ"))
    )
    (comp (ref "U$31")
      (value "APP_MOUTING_WINGHORIZ")
      (footprint "eagle-import:APP45_MOUNTING_WING_HORIZ")
      (libsource (lib "eagle-import") (part "APP_MOUTING_WINGHORIZ"))
    )
    (comp (ref "U$32")
      (value "APP_MOUTING_WINGHORIZ")
      (footprint "eagle-import:APP45_MOUNTING_WING_HORIZ")
      (libsource (lib "eagle-import") (part "APP_MOUTING_WINGHORIZ"))
    )
    (comp (ref "U$33")
      (value "APP_MOUTING_WINGHORIZ")
      (footprint "eagle-import:APP45_MOUNTING_WING_HORIZ")
      (libsource (lib "eagle-import") (part "APP_MOUTING_WINGHORIZ"))
    )
    (comp (ref "U$34")
      (value "APP_MOUTING_WINGHORIZ")
      (footprint "eagle-import:APP45_MOUNTING_WING_HORIZ")
      (libsource (lib "eagle-import") (part "APP_MOUTING_WINGHORIZ"))
    )
    (comp (ref "U$35")
      (value "APP_MOUTING_WINGHORIZ")
      (footprint "eagle-import:APP45_MOUNTING_WING_HORIZ")
      (libsource (lib "eagle-import") (part "APP_MOUTING_WINGHORIZ"))
    )
    (comp (ref "U$41")
      (value "APP_MOUTING_WINGHORIZ")
      (footprint "eagle-import:APP45_MOUNTING_WING_HORIZ")
      (libsource (lib "eagle-import") (part "APP_MOUTING_WINGHORIZ"))
    )
    (comp (ref "U$42")
      (value "APP_MOUTING_WINGHORIZ")
      (footprint "eagle-import:APP45_MOUNTING_WING_HORIZ")
      (libsource (lib "eagle-import") (part "APP_MOUTING_WINGHORIZ"))
    )
  )
  (nets
    (net (code "1") (name "+5V") (class "Default")
      (node (ref "5V-INT") (pin "R") (pinfunction "R_R") (pintype "bidirectional"))
      (node (ref "ACS714-M1") (pin "8") (pinfunction "VCC_8") (pintype "bidirectional"))
      (node (ref "ACS714-M2") (pin "8") (pinfunction "VCC_8") (pintype "bidirectional"))
      (node (ref "ACS714-M3") (pin "8") (pinfunction "VCC_8") (pintype "bidirectional"))
      (node (ref "ACS714-M4") (pin "8") (pinfunction "VCC_8") (pintype "bidirectional"))
      (node (ref "ACS714-M5") (pin "8") (pinfunction "VCC_8") (pintype "bidirectional"))
      (node (ref "ACS714-M6") (pin "8") (pinfunction "VCC_8") (pintype "bidirectional"))
      (node (ref "ACS714-M7") (pin "8") (pinfunction "VCC_8") (pintype "bidirectional"))
      (node (ref "ACS714-M8") (pin "8") (pinfunction "VCC_8") (pintype "bidirectional"))
      (node (ref "ACS714CAP-M1") (pin "2") (pinfunction "2_2") (pintype "passive"))
      (node (ref "ACS714CAP-M2") (pin "2") (pinfunction "2_2") (pintype "passive"))
      (node (ref "ACS714CAP-M3") (pin "2") (pinfunction "2_2") (pintype "passive"))
      (node (ref "ACS714CAP-M4") (pin "2") (pinfunction "2_2") (pintype "passive"))
      (node (ref "ACS714CAP-M5") (pin "2") (pinfunction "2_2") (pintype "passive"))
      (node (ref "ACS714CAP-M6") (pin "2") (pinfunction "2_2") (pintype "passive"))
      (node (ref "ACS714CAP-M7") (pin "2") (pinfunction "2_2") (pintype "passive"))
      (node (ref "ACS714CAP-M8") (pin "2") (pinfunction "2_2") (pintype "passive"))
      (node (ref "BB-8-5V") (pin "3") (pinfunction "VO_3") (pintype "bidirectional"))
      (node (ref "C11") (pin "2") (pinfunction "2_2") (pintype "passive"))
      (node (ref "C47") (pin "1") (pinfunction "1_1") (pintype "passive"))
      (node (ref "C48") (pin "1") (pinfunction "1_1") (pintype "passive"))
      (node (ref "C49") (pin "1") (pinfunction "1_1") (pintype "passive"))
      (node (ref "C6") (pin "2") (pinfunction "2_2") (pintype "passive"))
      (node (ref "LED5") (pin "A") (pinfunction "A_A") (pintype "passive"))
      (node (ref "U$1") (pin "+5V_1") (pinfunction "+5V_+5V_1") (pintype "bidirectional"))
      (node (ref "U$1") (pin "+5V_2") (pinfunction "+5V_+5V_2") (pintype "bidirectional"))
      (node (ref "U$12") (pin "VCC") (pinfunction "VCC_VCC") (pintype "bidirectional"))
      (node (ref "U$21") (pin "8") (pinfunction "VCC_8") (pintype "bidirectional"))
      (node (ref "U$24") (pin "VCC") (pinfunction "VCC_VCC") (pintype "bidirectional"))
      (node (ref "U$3") (pin "8") (pinfunction "VCC_8") (pintype "bidirectional"))
    )
    (net (code "2") (name "/RX1") (class "Default")
      (node (ref "U$1") (pin "PC4") (pinfunction "PC4_PC4") (pintype "bidirectional"))
      (node (ref "U$24") (pin "RO") (pinfunction "R0_RO") (pintype "bidirectional"))
    )
    (net (code "3") (name "/RX2") (class "Default")
      (node (ref "U$1") (pin "PP0") (pinfunction "PP0_PP0") (pintype "bidirectional"))
      (node (ref "U$12") (pin "RO") (pinfunction "R0_RO") (pintype "bidirectional"))
    )
    (net (code "4") (name "/TX1") (class "Default")
      (node (ref "U$1") (pin "PC5") (pinfunction "PC5_PC5") (pintype "bidirectional"))
      (node (ref "U$24") (pin "DI") (pinfunction "DI_DI") (pintype "bidirectional"))
    )
    (net (code "5") (name "/TX2") (class "Default")
      (node (ref "U$1") (pin "PP1") (pinfunction "PP1_PP1") (pintype "bidirectional"))
      (node (ref "U$12") (pin "DI") (pinfunction "DI_DI") (pintype "bidirectional"))
    )
    (net (code "6") (name "5V-AUX") (class "Default")
      (node (ref "R8") (pin "1") (pinfunction "1_1") (pintype "passive"))
      (node (ref "U$27") (pin "P$2") (pinfunction "P$1_P$2") (pintype "bidirectional"))
      (node (ref "U$3") (pin "4") (pinfunction "IP-_4") (pintype "bidirectional"))
    )
    (net (code "7") (name "12V-AUX") (class "Default")
      (node (ref "R10") (pin "1") (pinfunction "1_1") (pintype "passive"))
      (node (ref "U$21") (pin "4") (pinfunction "IP-_4") (pintype "bidirectional"))
      (node (ref "U$26") (pin "P$2") (pinfunction "P$1_P$2") (pintype "bidirectional"))
    )
    (net (code "8") (name "GND") (class "Default")
      (node (ref "5V-INT") (pin "L") (pinfunction "L_L") (pintype "bidirectional"))
      (node (ref "ACS714-M1") (pin "5") (pinfunction "GND_5") (pintype "bidirectional"))
      (node (ref "ACS714-M2") (pin "5") (pinfunction "GND_5") (pintype "bidirectional"))
      (node (ref "ACS714-M3") (pin "5") (pinfunction "GND_5") (pintype "bidirectional"))
      (node (ref "ACS714-M4") (pin "5") (pinfunction "GND_5") (pintype "bidirectional"))
      (node (ref "ACS714-M5") (pin "5") (pinfunction "GND_5") (pintype "bidirectional"))
      (node (ref "ACS714-M6") (pin "5") (pinfunction "GND_5") (pintype "bidirectional"))
      (node (ref "ACS714-M7") (pin "5") (pinfunction "GND_5") (pintype "bidirectional"))
      (node (ref "ACS714-M8") (pin "5") (pinfunction "GND_5") (pintype "bidirectional"))
      (node (ref "ACS714CAP-M1") (pin "1") (pinfunction "1_1") (pintype "passive"))
      (node (ref "ACS714CAP-M2") (pin "1") (pinfunction "1_1") (pintype "passive"))
      (node (ref "ACS714CAP-M3") (pin "1") (pinfunction "1_1") (pintype "passive"))
      (node (ref "ACS714CAP-M4") (pin "1") (pinfunction "1_1") (pintype "passive"))
      (node (ref "ACS714CAP-M5") (pin "1") (pinfunction "1_1") (pintype "passive"))
      (node (ref "ACS714CAP-M6") (pin "1") (pinfunction "1_1") (pintype "passive"))
      (node (ref "ACS714CAP-M7") (pin "1") (pinfunction "1_1") (pintype "passive"))
      (node (ref "ACS714CAP-M8") (pin "1") (pinfunction "1_1") (pintype "passive"))
      (node (ref "BATT-NEG") (pin "P$1") (pinfunction "P$1_P$1") (pintype "bidirectional"))
      (node (ref "BB-8-5V") (pin "2") (pinfunction "GND_2") (pintype "bidirectional"))
      (node (ref "BOTAPP-M1") (pin "P$1") (pinfunction "P$1_P$1") (pintype "bidirectional"))
      (node (ref "BOTAPP-M2") (pin "P$1") (pinfunction "P$1_P$1") (pintype "bidirectional"))
      (node (ref "BOTAPP-M3") (pin "P$1") (pinfunction "P$1_P$1") (pintype "bidirectional"))
      (node (ref "BOTAPP-M4") (pin "P$1") (pinfunction "P$1_P$1") (pintype "bidirectional"))
      (node (ref "BOTAPP-M5") (pin "P$1") (pinfunction "P$1_P$1") (pintype "bidirectional"))
      (node (ref "BOTAPP-M6") (pin "P$1") (pinfunction "P$1_P$1") (pintype "bidirectional"))
      (node (ref "BOTAPP-M7") (pin "P$1") (pinfunction "P$1_P$1") (pintype "bidirectional"))
      (node (ref "BOTAPP-M8") (pin "P$1") (pinfunction "P$1_P$1") (pintype "bidirectional"))
      (node (ref "C1") (pin "-") (pinfunction "-_-") (pintype "passive"))
      (node (ref "C11") (pin "1") (pinfunction "1_1") (pintype "passive"))
      (node (ref "C12") (pin "2") (pinfunction "2_2") (pintype "passive"))
      (node (ref "C13") (pin "2") (pinfunction "2_2") (pintype "passive"))
      (node (ref "C14") (pin "2") (pinfunction "2_2") (pintype "passive"))
      (node (ref "C15") (pin "2") (pinfunction "2_2") (pintype "passive"))
      (node (ref "C17") (pin "2") (pinfunction "2_2") (pintype "passive"))
      (node (ref "C18") (pin "2") (pinfunction "2_2") (pintype "passive"))
      (node (ref "C19") (pin "2") (pinfunction "2_2") (pintype "passive"))
      (node (ref "C2") (pin "-") (pinfunction "-_-") (pintype "passive"))
      (node (ref "C20") (pin "2") (pinfunction "2_2") (pintype "passive"))
      (node (ref "C21") (pin "2") (pinfunction "2_2") (pintype "passive"))
      (node (ref "C22") (pin "2") (pinfunction "2_2") (pintype "passive"))
      (node (ref "C3") (pin "-") (pinfunction "-_-") (pintype "passive"))
      (node (ref "C34") (pin "2") (pinfunction "2_2") (pintype "passive"))
      (node (ref "C4") (pin "-") (pinfunction "-_-") (pintype "passive"))
      (node (ref "C43") (pin "2") (pinfunction "2_2") (pintype "passive"))
      (node (ref "C44") (pin "2") (pinfunction "2_2") (pintype "passive"))
      (node (ref "C45") (pin "-") (pinfunction "-_-") (pintype "passive"))
      (node (ref "C46") (pin "-") (pinfunction "-_-") (pintype "passive"))
      (node (ref "C47") (pin "2") (pinfunction "2_2") (pintype "passive"))
      (node (ref "C48") (pin "2") (pinfunction "2_2") (pintype "passive"))
      (node (ref "C49") (pin "2") (pinfunction "2_2") (pintype "passive"))
      (node (ref "C50") (pin "2") (pinfunction "2_2") (pintype "passive"))
      (node (ref "C51") (pin "2") (pinfunction "2_2") (pintype "passive"))
      (node (ref "C52") (pin "2") (pinfunction "2_2") (pintype "passive"))
      (node (ref "C53") (pin "2") (pinfunction "2_2") (pintype "passive"))
      (node (ref "C6") (pin "1") (pinfunction "1_1") (pintype "passive"))
      (node (ref "D1") (pin "A") (pinfunction "A_A") (pintype "passive"))
      (node (ref "D2") (pin "A") (pinfunction "A_A") (pintype "passive"))
      (node (ref "FILTERCAP-M1") (pin "2") (pinfunction "2_2") (pintype "passive"))
      (node (ref "FILTERCAP-M2") (pin "2") (pinfunction "2_2") (pintype "passive"))
      (node (ref "FILTERCAP-M3") (pin "2") (pinfunction "2_2") (pintype "passive"))
      (node (ref "FILTERCAP-M4") (pin "2") (pinfunction "2_2") (pintype "passive"))
      (node (ref "FILTERCAP-M5") (pin "2") (pinfunction "2_2") (pintype "passive"))
      (node (ref "FILTERCAP-M6") (pin "2") (pinfunction "2_2") (pintype "passive"))
      (node (ref "FILTERCAP-M7") (pin "2") (pinfunction "2_2") (pintype "passive"))
      (node (ref "FILTERCAP-M8") (pin "2") (pinfunction "2_2") (pintype "passive"))
      (node (ref "FINN-12V") (pin "3") (pinfunction "-VIN_3") (pintype "bidirectional"))
      (node (ref "FINN-12V") (pin "4") (pinfunction "-VOUT_4") (pintype "bidirectional"))
      (node (ref "LED-M1") (pin "C") (pinfunction "C_C") (pintype "passive"))
      (node (ref "LED-M2") (pin "C") (pinfunction "C_C") (pintype "passive"))
      (node (ref "LED-M3") (pin "C") (pinfunction "C_C") (pintype "passive"))
      (node (ref "LED-M4") (pin "C") (pinfunction "C_C") (pintype "passive"))
      (node (ref "LED-M5") (pin "C") (pinfunction "C_C") (pintype "passive"))
      (node (ref "LED-M6") (pin "C") (pinfunction "C_C") (pintype "passive"))
      (node (ref "LED-M7") (pin "C") (pinfunction "C_C") (pintype "passive"))
      (node (ref "LED-M8") (pin "C") (pinfunction "C_C") (pintype "passive"))
      (node (ref "LED2") (pin "C") (pinfunction "C_C") (pintype "passive"))
      (node (ref "LED3") (pin "C") (pinfunction "C_C") (pintype "passive"))
      (node (ref "LT1910-M1") (pin "1") (pinfunction "GND_1") (pintype "bidirectional"))
      (node (ref "LT1910-M2") (pin "1") (pinfunction "GND_1") (pintype "bidirectional"))
      (node (ref "LT1910-M3") (pin "1") (pinfunction "GND_1") (pintype "bidirectional"))
      (node (ref "LT1910-M4") (pin "1") (pinfunction "GND_1") (pintype "bidirectional"))
      (node (ref "LT1910-M5") (pin "1") (pinfunction "GND_1") (pintype "bidirectional"))
      (node (ref "LT1910-M6") (pin "1") (pinfunction "GND_1") (pintype "bidirectional"))
      (node (ref "LT1910-M7") (pin "1") (pinfunction "GND_1") (pintype "bidirectional"))
      (node (ref "LT1910-M8") (pin "1") (pinfunction "GND_1") (pintype "bidirectional"))
      (node (ref "LT1910CAP-M1") (pin "1") (pinfunction "1_1") (pintype "passive"))
      (node (ref "LT1910CAP-M2") (pin "1") (pinfunction "1_1") (pintype "passive"))
      (node (ref "LT1910CAP-M3") (pin "1") (pinfunction "1_1") (pintype "passive"))
      (node (ref "LT1910CAP-M4") (pin "1") (pinfunction "1_1") (pintype "passive"))
      (node (ref "LT1910CAP-M5") (pin "1") (pinfunction "1_1") (pintype "passive"))
      (node (ref "LT1910CAP-M6") (pin "1") (pinfunction "1_1") (pintype "passive"))
      (node (ref "LT1910CAP-M7") (pin "1") (pinfunction "1_1") (pintype "passive"))
      (node (ref "LT1910CAP-M8") (pin "1") (pinfunction "1_1") (pintype "passive"))
      (node (ref "POE-12V") (pin "3") (pinfunction "-VIN_3") (pintype "bidirectional"))
      (node (ref "POE-12V") (pin "4") (pinfunction "-VOUT_4") (pintype "bidirectional"))
      (node (ref "Q12") (pin "2") (pinfunction "S_2") (pintype "passive"))
      (node (ref "Q2") (pin "2") (pinfunction "S_2") (pintype "passive"))
      (node (ref "R13") (pin "2") (pinfunction "2_2") (pintype "passive"))
      (node (ref "R4") (pin "1") (pinfunction "1_1") (pintype "passive"))
      (node (ref "REY-5V") (pin "P$2") (pinfunction "-VIN_P$2") (pintype "bidirectional"))
      (node (ref "REY-5V") (pin "P$5") (pinfunction "-VOUT_P$5") (pintype "bidirectional"))
      (node (ref "REY-5V") (pin "P$8") (pinfunction "-SENSE_P$8") (pintype "bidirectional"))
      (node (ref "U$1") (pin "GND_1") (pinfunction "GND_GND_1") (pintype "bidirectional"))
      (node (ref "U$1") (pin "GND_2") (pinfunction "GND_GND_2") (pintype "bidirectional"))
      (node (ref "U$1") (pin "GND_3") (pinfunction "GND_GND_3") (pintype "bidirectional"))
      (node (ref "U$1") (pin "GND_4") (pinfunction "GND_GND_4") (pintype "bidirectional"))
      (node (ref "U$12") (pin "GND") (pinfunction "GND_GND") (pintype "bidirectional"))
      (node (ref "U$21") (pin "5") (pinfunction "GND_5") (pintype "bidirectional"))
      (node (ref "U$24") (pin "GND") (pinfunction "GND_GND") (pintype "bidirectional"))
      (node (ref "U$28") (pin "P$1") (pinfunction "P$1_P$1") (pintype "bidirectional"))
      (node (ref "U$29") (pin "P$1") (pinfunction "P$1_P$1") (pintype "bidirectional"))
      (node (ref "U$3") (pin "5") (pinfunction "GND_5") (pintype "bidirectional"))
      (node (ref "U$5") (pin "7") (pinfunction "7_7") (pintype "bidirectional"))
      (node (ref "U$5") (pin "8") (pinfunction "8_8") (pintype "bidirectional"))
      (node (ref "U$6") (pin "7") (pinfunction "7_7") (pintype "bidirectional"))
      (node (ref "U$6") (pin "8") (pinfunction "8_8") (pintype "bidirectional"))
    )
    (net (code "9") (name "IMEAS-5V") (class "Default")
      (node (ref "U$1") (pin "PE2") (pinfunction "PE2_PE2") (pintype "bidirectional"))
      (node (ref "U$3") (pin "7") (pinfunction "VIOUT_7") (pintype "bidirectional"))
    )
    (net (code "10") (name "IMEAS-12V") (class "Default")
      (node (ref "U$1") (pin "PD7") (pinfunction "PD7_PD7") (pintype "bidirectional"))
      (node (ref "U$21") (pin "7") (pinfunction "VIOUT_7") (pintype "bidirectional"))
    )
    (net (code "11") (name "IMEAS-M1") (class "Default")
      (node (ref "ACS714-M1") (pin "7") (pinfunction "VIOUT_7") (pintype "bidirectional"))
      (node (ref "U$1") (pin "PK3") (pinfunction "PK3_PK3") (pintype "bidirectional"))
    )
    (net (code "12") (name "IMEAS-M2") (class "Default")
      (node (ref "ACS714-M2") (pin "7") (pinfunction "VIOUT_7") (pintype "bidirectional"))
      (node (ref "U$1") (pin "PK2") (pinfunction "PK2_PK2") (pintype "bidirectional"))
    )
    (net (code "13") (name "IMEAS-M3") (class "Default")
      (node (ref "ACS714-M3") (pin "7") (pinfunction "VIOUT_7") (pintype "bidirectional"))
      (node (ref "U$1") (pin "PK1") (pinfunction "PK1_PK1") (pintype "bidirectional"))
    )
    (net (code "14") (name "IMEAS-M4") (class "Default")
      (node (ref "ACS714-M4") (pin "7") (pinfunction "VIOUT_7") (pintype "bidirectional"))
      (node (ref "U$1") (pin "PD4") (pinfunction "PD4_PD4") (pintype "bidirectional"))
    )
    (net (code "15") (name "IMEAS-M5") (class "Default")
      (node (ref "ACS714-M5") (pin "7") (pinfunction "VIOUT_7") (pintype "bidirectional"))
      (node (ref "U$1") (pin "PK0") (pinfunction "PK0_PK0") (pintype "bidirectional"))
    )
    (net (code "16") (name "IMEAS-M6") (class "Default")
      (node (ref "ACS714-M6") (pin "7") (pinfunction "VIOUT_7") (pintype "bidirectional"))
      (node (ref "U$1") (pin "PB5") (pinfunction "PB5_PB5") (pintype "bidirectional"))
    )
    (net (code "17") (name "IMEAS-M7") (class "Default")
      (node (ref "ACS714-M7") (pin "7") (pinfunction "VIOUT_7") (pintype "bidirectional"))
      (node (ref "U$1") (pin "PB4") (pinfunction "PB4_PB4") (pintype "bidirectional"))
    )
    (net (code "18") (name "IMEAS-M8") (class "Default")
      (node (ref "ACS714-M8") (pin "7") (pinfunction "VIOUT_7") (pintype "bidirectional"))
      (node (ref "U$1") (pin "PD2") (pinfunction "PD2_PD2") (pintype "bidirectional"))
    )
    (net (code "19") (name "Net-(ACS714-M1-FILTER)") (class "Default")
      (node (ref "ACS714-M1") (pin "6") (pinfunction "FILTER_6") (pintype "bidirectional"))
      (node (ref "FILTERCAP-M1") (pin "1") (pinfunction "1_1") (pintype "passive"))
    )
    (net (code "20") (name "Net-(ACS714-M1-IP-)") (class "Default")
      (node (ref "ACS714-M1") (pin "4") (pinfunction "IP-_4") (pintype "bidirectional"))
      (node (ref "FET-M1") (pin "TAB") (pinfunction "D_TAB") (pintype "bidirectional"))
      (node (ref "LT1910-M1") (pin "6") (pinfunction "SENSE_6") (pintype "bidirectional"))
      (node (ref "LT1910-M1") (pin "8") (pinfunction "V+_8") (pintype "bidirectional"))
      (node (ref "LT1910CAP-M1") (pin "2") (pinfunction "2_2") (pintype "passive"))
    )
    (net (code "21") (name "Net-(ACS714-M2-FILTER)") (class "Default")
      (node (ref "ACS714-M2") (pin "6") (pinfunction "FILTER_6") (pintype "bidirectional"))
      (node (ref "FILTERCAP-M2") (pin "1") (pinfunction "1_1") (pintype "passive"))
    )
    (net (code "22") (name "Net-(ACS714-M2-IP-)") (class "Default")
      (node (ref "ACS714-M2") (pin "4") (pinfunction "IP-_4") (pintype "bidirectional"))
      (node (ref "FET-M2") (pin "TAB") (pinfunction "D_TAB") (pintype "bidirectional"))
      (node (ref "LT1910-M2") (pin "6") (pinfunction "SENSE_6") (pintype "bidirectional"))
      (node (ref "LT1910-M2") (pin "8") (pinfunction "V+_8") (pintype "bidirectional"))
      (node (ref "LT1910CAP-M2") (pin "2") (pinfunction "2_2") (pintype "passive"))
    )
    (net (code "23") (name "Net-(ACS714-M3-FILTER)") (class "Default")
      (node (ref "ACS714-M3") (pin "6") (pinfunction "FILTER_6") (pintype "bidirectional"))
      (node (ref "FILTERCAP-M3") (pin "1") (pinfunction "1_1") (pintype "passive"))
    )
    (net (code "24") (name "Net-(ACS714-M3-IP-)") (class "Default")
      (node (ref "ACS714-M3") (pin "4") (pinfunction "IP-_4") (pintype "bidirectional"))
      (node (ref "FET-M3") (pin "TAB") (pinfunction "D_TAB") (pintype "bidirectional"))
      (node (ref "LT1910-M3") (pin "6") (pinfunction "SENSE_6") (pintype "bidirectional"))
      (node (ref "LT1910-M3") (pin "8") (pinfunction "V+_8") (pintype "bidirectional"))
      (node (ref "LT1910CAP-M3") (pin "2") (pinfunction "2_2") (pintype "passive"))
    )
    (net (code "25") (name "Net-(ACS714-M4-FILTER)") (class "Default")
      (node (ref "ACS714-M4") (pin "6") (pinfunction "FILTER_6") (pintype "bidirectional"))
      (node (ref "FILTERCAP-M4") (pin "1") (pinfunction "1_1") (pintype "passive"))
    )
    (net (code "26") (name "Net-(ACS714-M4-IP-)") (class "Default")
      (node (ref "ACS714-M4") (pin "4") (pinfunction "IP-_4") (pintype "bidirectional"))
      (node (ref "FET-M4") (pin "TAB") (pinfunction "D_TAB") (pintype "bidirectional"))
      (node (ref "LT1910-M4") (pin "6") (pinfunction "SENSE_6") (pintype "bidirectional"))
      (node (ref "LT1910-M4") (pin "8") (pinfunction "V+_8") (pintype "bidirectional"))
      (node (ref "LT1910CAP-M4") (pin "2") (pinfunction "2_2") (pintype "passive"))
    )
    (net (code "27") (name "Net-(ACS714-M5-FILTER)") (class "Default")
      (node (ref "ACS714-M5") (pin "6") (pinfunction "FILTER_6") (pintype "bidirectional"))
      (node (ref "FILTERCAP-M5") (pin "1") (pinfunction "1_1") (pintype "passive"))
    )
    (net (code "28") (name "Net-(ACS714-M5-IP-)") (class "Default")
      (node (ref "ACS714-M5") (pin "4") (pinfunction "IP-_4") (pintype "bidirectional"))
      (node (ref "FET-M5") (pin "TAB") (pinfunction "D_TAB") (pintype "bidirectional"))
      (node (ref "LT1910-M5") (pin "6") (pinfunction "SENSE_6") (pintype "bidirectional"))
      (node (ref "LT1910-M5") (pin "8") (pinfunction "V+_8") (pintype "bidirectional"))
      (node (ref "LT1910CAP-M5") (pin "2") (pinfunction "2_2") (pintype "passive"))
    )
    (net (code "29") (name "Net-(ACS714-M6-FILTER)") (class "Default")
      (node (ref "ACS714-M6") (pin "6") (pinfunction "FILTER_6") (pintype "bidirectional"))
      (node (ref "FILTERCAP-M6") (pin "1") (pinfunction "1_1") (pintype "passive"))
    )
    (net (code "30") (name "Net-(ACS714-M6-IP-)") (class "Default")
      (node (ref "ACS714-M6") (pin "4") (pinfunction "IP-_4") (pintype "bidirectional"))
      (node (ref "FET-M6") (pin "TAB") (pinfunction "D_TAB") (pintype "bidirectional"))
      (node (ref "LT1910-M6") (pin "6") (pinfunction "SENSE_6") (pintype "bidirectional"))
      (node (ref "LT1910-M6") (pin "8") (pinfunction "V+_8") (pintype "bidirectional"))
      (node (ref "LT1910CAP-M6") (pin "2") (pinfunction "2_2") (pintype "passive"))
    )
    (net (code "31") (name "Net-(ACS714-M7-FILTER)") (class "Default")
      (node (ref "ACS714-M7") (pin "6") (pinfunction "FILTER_6") (pintype "bidirectional"))
      (node (ref "FILTERCAP-M7") (pin "1") (pinfunction "1_1") (pintype "passive"))
    )
    (net (code "32") (name "Net-(ACS714-M7-IP-)") (class "Default")
      (node (ref "ACS714-M7") (pin "4") (pinfunction "IP-_4") (pintype "bidirectional"))
      (node (ref "FET-M7") (pin "TAB") (pinfunction "D_TAB") (pintype "bidirectional"))
      (node (ref "LT1910-M7") (pin "6") (pinfunction "SENSE_6") (pintype "bidirectional"))
      (node (ref "LT1910-M7") (pin "8") (pinfunction "V+_8") (pintype "bidirectional"))
      (node (ref "LT1910CAP-M7") (pin "2") (pinfunction "2_2") (pintype "passive"))
    )
    (net (code "33") (name "Net-(ACS714-M8-FILTER)") (class "Default")
      (node (ref "ACS714-M8") (pin "6") (pinfunction "FILTER_6") (pintype "bidirectional"))
      (node (ref "FILTERCAP-M8") (pin "1") (pinfunction "1_1") (pintype "passive"))
    )
    (net (code "34") (name "Net-(ACS714-M8-IP-)") (class "Default")
      (node (ref "ACS714-M8") (pin "4") (pinfunction "IP-_4") (pintype "bidirectional"))
      (node (ref "FET-M8") (pin "TAB") (pinfunction "D_TAB") (pintype "bidirectional"))
      (node (ref "LT1910-M8") (pin "6") (pinfunction "SENSE_6") (pintype "bidirectional"))
      (node (ref "LT1910-M8") (pin "8") (pinfunction "V+_8") (pintype "bidirectional"))
      (node (ref "LT1910CAP-M8") (pin "2") (pinfunction "2_2") (pintype "passive"))
    )
    (net (code "35") (name "Net-(FET-M1-G)") (class "Default")
      (node (ref "FET-M1") (pin "1") (pinfunction "G_1") (pintype "bidirectional"))
      (node (ref "LT1910-M1") (pin "5") (pinfunction "GATE_5") (pintype "bidirectional"))
    )
    (net (code "36") (name "Net-(FET-M1-S)") (class "Default")
      (node (ref "FET-M1") (pin "2") (pinfunction "S_2") (pintype "bidirectional"))
      (node (ref "LEDRES-M1") (pin "1") (pinfunction "1_1") (pintype "passive"))
      (node (ref "TOPAPP-M1") (pin "P$2") (pinfunction "P$1_P$2") (pintype "bidirectional"))
    )
    (net (code "37") (name "Net-(FET-M2-G)") (class "Default")
      (node (ref "FET-M2") (pin "1") (pinfunction "G_1") (pintype "bidirectional"))
      (node (ref "LT1910-M2") (pin "5") (pinfunction "GATE_5") (pintype "bidirectional"))
    )
    (net (code "38") (name "Net-(FET-M2-S)") (class "Default")
      (node (ref "FET-M2") (pin "2") (pinfunction "S_2") (pintype "bidirectional"))
      (node (ref "LEDRES-M2") (pin "1") (pinfunction "1_1") (pintype "passive"))
      (node (ref "TOPAPP-M2") (pin "P$2") (pinfunction "P$1_P$2") (pintype "bidirectional"))
    )
    (net (code "39") (name "Net-(FET-M3-G)") (class "Default")
      (node (ref "FET-M3") (pin "1") (pinfunction "G_1") (pintype "bidirectional"))
      (node (ref "LT1910-M3") (pin "5") (pinfunction "GATE_5") (pintype "bidirectional"))
    )
    (net (code "40") (name "Net-(FET-M3-S)") (class "Default")
      (node (ref "FET-M3") (pin "2") (pinfunction "S_2") (pintype "bidirectional"))
      (node (ref "LEDRES-M3") (pin "1") (pinfunction "1_1") (pintype "passive"))
      (node (ref "TOPAPP-M3") (pin "P$2") (pinfunction "P$1_P$2") (pintype "bidirectional"))
    )
    (net (code "41") (name "Net-(FET-M4-G)") (class "Default")
      (node (ref "FET-M4") (pin "1") (pinfunction "G_1") (pintype "bidirectional"))
      (node (ref "LT1910-M4") (pin "5") (pinfunction "GATE_5") (pintype "bidirectional"))
    )
    (net (code "42") (name "Net-(FET-M4-S)") (class "Default")
      (node (ref "FET-M4") (pin "2") (pinfunction "S_2") (pintype "bidirectional"))
      (node (ref "LEDRES-M4") (pin "1") (pinfunction "1_1") (pintype "passive"))
      (node (ref "TOPAPP-M4") (pin "P$2") (pinfunction "P$1_P$2") (pintype "bidirectional"))
    )
    (net (code "43") (name "Net-(FET-M5-G)") (class "Default")
      (node (ref "FET-M5") (pin "1") (pinfunction "G_1") (pintype "bidirectional"))
      (node (ref "LT1910-M5") (pin "5") (pinfunction "GATE_5") (pintype "bidirectional"))
    )
    (net (code "44") (name "Net-(FET-M5-S)") (class "Default")
      (node (ref "FET-M5") (pin "2") (pinfunction "S_2") (pintype "bidirectional"))
      (node (ref "LEDRES-M5") (pin "1") (pinfunction "1_1") (pintype "passive"))
      (node (ref "TOPAPP-M5") (pin "P$2") (pinfunction "P$1_P$2") (pintype "bidirectional"))
    )
    (net (code "45") (name "Net-(FET-M6-G)") (class "Default")
      (node (ref "FET-M6") (pin "1") (pinfunction "G_1") (pintype "bidirectional"))
      (node (ref "LT1910-M6") (pin "5") (pinfunction "GATE_5") (pintype "bidirectional"))
    )
    (net (code "46") (name "Net-(FET-M6-S)") (class "Default")
      (node (ref "FET-M6") (pin "2") (pinfunction "S_2") (pintype "bidirectional"))
      (node (ref "LEDRES-M6") (pin "1") (pinfunction "1_1") (pintype "passive"))
      (node (ref "TOPAPP-M6") (pin "P$2") (pinfunction "P$1_P$2") (pintype "bidirectional"))
    )
    (net (code "47") (name "Net-(FET-M7-G)") (class "Default")
      (node (ref "FET-M7") (pin "1") (pinfunction "G_1") (pintype "bidirectional"))
      (node (ref "LT1910-M7") (pin "5") (pinfunction "GATE_5") (pintype "bidirectional"))
    )
    (net (code "48") (name "Net-(FET-M7-S)") (class "Default")
      (node (ref "FET-M7") (pin "2") (pinfunction "S_2") (pintype "bidirectional"))
      (node (ref "LEDRES-M7") (pin "1") (pinfunction "1_1") (pintype "passive"))
      (node (ref "TOPAPP-M7") (pin "P$2") (pinfunction "P$1_P$2") (pintype "bidirectional"))
    )
    (net (code "49") (name "Net-(FET-M8-G)") (class "Default")
      (node (ref "FET-M8") (pin "1") (pinfunction "G_1") (pintype "bidirectional"))
      (node (ref "LT1910-M8") (pin "5") (pinfunction "GATE_5") (pintype "bidirectional"))
    )
    (net (code "50") (name "Net-(FET-M8-S)") (class "Default")
      (node (ref "FET-M8") (pin "2") (pinfunction "S_2") (pintype "bidirectional"))
      (node (ref "LEDRES-M8") (pin "1") (pinfunction "1_1") (pintype "passive"))
      (node (ref "TOPAPP-M8") (pin "P$2") (pinfunction "P$1_P$2") (pintype "bidirectional"))
    )
    (net (code "51") (name "Net-(FINN-12V-+VOUT)") (class "Default")
      (node (ref "C19") (pin "1") (pinfunction "1_1") (pintype "passive"))
      (node (ref "C20") (pin "1") (pinfunction "1_1") (pintype "passive"))
      (node (ref "C45") (pin "+") (pinfunction "+_+") (pintype "passive"))
      (node (ref "C46") (pin "+") (pinfunction "+_+") (pintype "passive"))
      (node (ref "FINN-12V") (pin "8") (pinfunction "+VOUT_8") (pintype "bidirectional"))
      (node (ref "POE-12V") (pin "8") (pinfunction "+VOUT_8") (pintype "bidirectional"))
      (node (ref "U$21") (pin "1") (pinfunction "IP+_1") (pintype "bidirectional"))
    )
    (net (code "52") (name "Net-(FINN-12V-REMOTE)") (class "Default")
      (node (ref "FINN-12V") (pin "2") (pinfunction "REMOTE_2") (pintype "bidirectional"))
      (node (ref "POE-12V") (pin "2") (pinfunction "REMOTE_2") (pintype "bidirectional"))
      (node (ref "Q12") (pin "3") (pinfunction "D_3") (pintype "passive"))
    )
    (net (code "53") (name "Net-(LED-M1-PadA)") (class "Default")
      (node (ref "LED-M1") (pin "A") (pinfunction "A_A") (pintype "passive"))
      (node (ref "LEDRES-M1") (pin "2") (pinfunction "2_2") (pintype "passive"))
    )
    (net (code "54") (name "Net-(LED-M2-PadA)") (class "Default")
      (node (ref "LED-M2") (pin "A") (pinfunction "A_A") (pintype "passive"))
      (node (ref "LEDRES-M2") (pin "2") (pinfunction "2_2") (pintype "passive"))
    )
    (net (code "55") (name "Net-(LED-M3-PadA)") (class "Default")
      (node (ref "LED-M3") (pin "A") (pinfunction "A_A") (pintype "passive"))
      (node (ref "LEDRES-M3") (pin "2") (pinfunction "2_2") (pintype "passive"))
    )
    (net (code "56") (name "Net-(LED-M4-PadA)") (class "Default")
      (node (ref "LED-M4") (pin "A") (pinfunction "A_A") (pintype "passive"))
      (node (ref "LEDRES-M4") (pin "2") (pinfunction "2_2") (pintype "passive"))
    )
    (net (code "57") (name "Net-(LED-M5-PadA)") (class "Default")
      (node (ref "LED-M5") (pin "A") (pinfunction "A_A") (pintype "passive"))
      (node (ref "LEDRES-M5") (pin "2") (pinfunction "2_2") (pintype "passive"))
    )
    (net (code "58") (name "Net-(LED-M6-PadA)") (class "Default")
      (node (ref "LED-M6") (pin "A") (pinfunction "A_A") (pintype "passive"))
      (node (ref "LEDRES-M6") (pin "2") (pinfunction "2_2") (pintype "passive"))
    )
    (net (code "59") (name "Net-(LED-M7-PadA)") (class "Default")
      (node (ref "LED-M7") (pin "A") (pinfunction "A_A") (pintype "passive"))
      (node (ref "LEDRES-M7") (pin "2") (pinfunction "2_2") (pintype "passive"))
    )
    (net (code "60") (name "Net-(LED-M8-PadA)") (class "Default")
      (node (ref "LED-M8") (pin "A") (pinfunction "A_A") (pintype "passive"))
      (node (ref "LEDRES-M8") (pin "2") (pinfunction "2_2") (pintype "passive"))
    )
    (net (code "61") (name "Net-(LED2-PadA)") (class "Default")
      (node (ref "LED2") (pin "A") (pinfunction "A_A") (pintype "passive"))
      (node (ref "R10") (pin "2") (pinfunction "2_2") (pintype "passive"))
    )
    (net (code "62") (name "Net-(LED3-PadA)") (class "Default")
      (node (ref "LED3") (pin "A") (pinfunction "A_A") (pintype "passive"))
      (node (ref "R8") (pin "2") (pinfunction "2_2") (pintype "passive"))
    )
    (net (code "63") (name "Net-(LED5-PadC)") (class "Default")
      (node (ref "LED5") (pin "C") (pinfunction "C_C") (pintype "passive"))
      (node (ref "R13") (pin "1") (pinfunction "1_1") (pintype "passive"))
    )
    (net (code "64") (name "Net-(Q2-D)") (class "Default")
      (node (ref "Q2") (pin "3") (pinfunction "D_3") (pintype "passive"))
      (node (ref "REY-5V") (pin "P$1") (pinfunction "ON/OFF_P$1") (pintype "bidirectional"))
    )
    (net (code "65") (name "Net-(Q2-G)") (class "Default")
      (node (ref "Q2") (pin "1") (pinfunction "G_1") (pintype "passive"))
      (node (ref "R11") (pin "1") (pinfunction "1_1") (pintype "passive"))
    )
    (net (code "66") (name "Net-(Q12-G)") (class "Default")
      (node (ref "Q12") (pin "1") (pinfunction "G_1") (pintype "passive"))
      (node (ref "R15") (pin "1") (pinfunction "1_1") (pintype "passive"))
    )
    (net (code "67") (name "Net-(R1-Pad1)") (class "Default")
      (node (ref "R1") (pin "1") (pinfunction "1_1") (pintype "passive"))
      (node (ref "U$12") (pin "A") (pinfunction "A_A") (pintype "bidirectional"))
      (node (ref "U$6") (pin "1") (pinfunction "1_1") (pintype "bidirectional"))
    )
    (net (code "68") (name "Net-(R1-Pad2)") (class "Default")
      (node (ref "R1") (pin "2") (pinfunction "2_2") (pintype "passive"))
      (node (ref "U$12") (pin "B") (pinfunction "B_B") (pintype "bidirectional"))
      (node (ref "U$6") (pin "2") (pinfunction "2_2") (pintype "bidirectional"))
    )
    (net (code "69") (name "Net-(R2-Pad1)") (class "Default")
      (node (ref "R2") (pin "1") (pinfunction "1_1") (pintype "passive"))
      (node (ref "U$24") (pin "A") (pinfunction "A_A") (pintype "bidirectional"))
      (node (ref "U$5") (pin "1") (pinfunction "1_1") (pintype "bidirectional"))
    )
    (net (code "70") (name "Net-(R2-Pad2)") (class "Default")
      (node (ref "R2") (pin "2") (pinfunction "2_2") (pintype "passive"))
      (node (ref "U$24") (pin "B") (pinfunction "B_B") (pintype "bidirectional"))
      (node (ref "U$5") (pin "2") (pinfunction "2_2") (pintype "bidirectional"))
    )
    (net (code "71") (name "Net-(R6-Pad1)") (class "Default")
      (node (ref "R6") (pin "1") (pinfunction "1_1") (pintype "passive"))
      (node (ref "U$12") (pin "Z") (pinfunction "Z_Z") (pintype "bidirectional"))
      (node (ref "U$6") (pin "6") (pinfunction "6_6") (pintype "bidirectional"))
    )
    (net (code "72") (name "Net-(R6-Pad2)") (class "Default")
      (node (ref "R6") (pin "2") (pinfunction "2_2") (pintype "passive"))
      (node (ref "U$12") (pin "Y") (pinfunction "Y_Y") (pintype "bidirectional"))
      (node (ref "U$6") (pin "3") (pinfunction "3_3") (pintype "bidirectional"))
    )
    (net (code "73") (name "Net-(R7-Pad1)") (class "Default")
      (node (ref "R7") (pin "1") (pinfunction "1_1") (pintype "passive"))
      (node (ref "U$24") (pin "Z") (pinfunction "Z_Z") (pintype "bidirectional"))
      (node (ref "U$5") (pin "6") (pinfunction "6_6") (pintype "bidirectional"))
    )
    (net (code "74") (name "Net-(R7-Pad2)") (class "Default")
      (node (ref "R7") (pin "2") (pinfunction "2_2") (pintype "passive"))
      (node (ref "U$24") (pin "Y") (pinfunction "Y_Y") (pintype "bidirectional"))
      (node (ref "U$5") (pin "3") (pinfunction "3_3") (pintype "bidirectional"))
    )
    (net (code "75") (name "Net-(REY-5V-+SENSE)") (class "Default")
      (node (ref "C13") (pin "1") (pinfunction "1_1") (pintype "passive"))
      (node (ref "C14") (pin "1") (pinfunction "1_1") (pintype "passive"))
      (node (ref "C15") (pin "1") (pinfunction "1_1") (pintype "passive"))
      (node (ref "C17") (pin "1") (pinfunction "1_1") (pintype "passive"))
      (node (ref "C34") (pin "1") (pinfunction "1_1") (pintype "passive"))
      (node (ref "C44") (pin "1") (pinfunction "1_1") (pintype "passive"))
      (node (ref "C50") (pin "1") (pinfunction "1_1") (pintype "passive"))
      (node (ref "C51") (pin "1") (pinfunction "1_1") (pintype "passive"))
      (node (ref "C52") (pin "1") (pinfunction "1_1") (pintype "passive"))
      (node (ref "C53") (pin "1") (pinfunction "1_1") (pintype "passive"))
      (node (ref "REY-5V") (pin "P$6") (pinfunction "+VOUT_P$6") (pintype "bidirectional"))
      (node (ref "REY-5V") (pin "P$7") (pinfunction "+SENSE_P$7") (pintype "bidirectional"))
      (node (ref "U$3") (pin "1") (pinfunction "IP+_1") (pintype "bidirectional"))
    )
    (net (code "76") (name "Net-(U$1-+3V3-Pad+3V3_1)") (class "Default")
      (node (ref "U$1") (pin "+3V3_1") (pinfunction "+3V3_+3V3_1") (pintype "bidirectional"))
      (node (ref "U$1") (pin "+3V3_2") (pinfunction "+3V3_+3V3_2") (pintype "bidirectional"))
    )
    (net (code "77") (name "Net-(U$1-RST-PadRST1)") (class "Default")
      (node (ref "U$1") (pin "RST1") (pinfunction "RST_RST1") (pintype "bidirectional"))
      (node (ref "U$1") (pin "RST_2") (pinfunction "RST_RST_2") (pintype "bidirectional"))
    )
    (net (code "78") (name "Net-(U$3-FILTER)") (class "Default")
      (node (ref "C12") (pin "1") (pinfunction "1_1") (pintype "passive"))
      (node (ref "U$3") (pin "6") (pinfunction "FILTER_6") (pintype "bidirectional"))
    )
    (net (code "79") (name "Net-(U$21-FILTER)") (class "Default")
      (node (ref "C43") (pin "1") (pinfunction "1_1") (pintype "passive"))
      (node (ref "U$21") (pin "6") (pinfunction "FILTER_6") (pintype "bidirectional"))
    )
    (net (code "80") (name "SIG-5V") (class "Default")
      (node (ref "R11") (pin "2") (pinfunction "2_2") (pintype "passive"))
      (node (ref "U$1") (pin "PP2") (pinfunction "PP2_PP2") (pintype "bidirectional"))
    )
    (net (code "81") (name "SIG-12V") (class "Default")
      (node (ref "R15") (pin "2") (pinfunction "2_2") (pintype "passive"))
      (node (ref "U$1") (pin "PN3") (pinfunction "PN3_PN3") (pintype "bidirectional"))
    )
    (net (code "82") (name "SIG-M1") (class "Default")
      (node (ref "LT1910-M1") (pin "4") (pinfunction "IN_4") (pintype "bidirectional"))
      (node (ref "U$1") (pin "PK7") (pinfunction "PK7_PK7") (pintype "bidirectional"))
    )
    (net (code "83") (name "SIG-M2") (class "Default")
      (node (ref "LT1910-M2") (pin "4") (pinfunction "IN_4") (pintype "bidirectional"))
      (node (ref "U$1") (pin "PQ1") (pinfunction "PQ1_PQ1") (pintype "bidirectional"))
    )
    (net (code "84") (name "SIG-M3") (class "Default")
      (node (ref "LT1910-M3") (pin "4") (pinfunction "IN_4") (pintype "bidirectional"))
      (node (ref "U$1") (pin "PK6") (pinfunction "PK6_PK6") (pintype "bidirectional"))
    )
    (net (code "85") (name "SIG-M4") (class "Default")
      (node (ref "LT1910-M4") (pin "4") (pinfunction "IN_4") (pintype "bidirectional"))
      (node (ref "U$1") (pin "PP3") (pinfunction "PP3_PP3") (pintype "bidirectional"))
    )
    (net (code "86") (name "SIG-M5") (class "Default")
      (node (ref "LT1910-M5") (pin "4") (pinfunction "IN_4") (pintype "bidirectional"))
      (node (ref "U$1") (pin "PH1") (pinfunction "PH1_PH1") (pintype "bidirectional"))
    )
    (net (code "87") (name "SIG-M6") (class "Default")
      (node (ref "LT1910-M6") (pin "4") (pinfunction "IN_4") (pintype "bidirectional"))
      (node (ref "U$1") (pin "PH0") (pinfunction "PH0_PH0") (pintype "bidirectional"))
    )
    (net (code "88") (name "SIG-M7") (class "Default")
      (node (ref "LT1910-M7") (pin "4") (pinfunction "IN_4") (pintype "bidirectional"))
      (node (ref "U$1") (pin "PA7") (pinfunction "PA7_PA7") (pintype "bidirectional"))
    )
    (net (code "89") (name "SIG-M8") (class "Default")
      (node (ref "LT1910-M8") (pin "4") (pinfunction "IN_4") (pintype "bidirectional"))
      (node (ref "U$1") (pin "PP5") (pinfunction "PP5_PP5") (pintype "bidirectional"))
    )
    (net (code "90") (name "VMEAS-VBATT") (class "Default")
      (node (ref "R3") (pin "1") (pinfunction "1_1") (pintype "passive"))
      (node (ref "R4") (pin "2") (pinfunction "2_2") (pintype "passive"))
      (node (ref "U$1") (pin "PE3") (pinfunction "PE3_PE3") (pintype "bidirectional"))
    )
    (net (code "91") (name "V_BATT") (class "Default")
      (node (ref "ACS714-M1") (pin "1") (pinfunction "IP+_1") (pintype "bidirectional"))
      (node (ref "ACS714-M2") (pin "1") (pinfunction "IP+_1") (pintype "bidirectional"))
      (node (ref "ACS714-M3") (pin "1") (pinfunction "IP+_1") (pintype "bidirectional"))
      (node (ref "ACS714-M4") (pin "1") (pinfunction "IP+_1") (pintype "bidirectional"))
      (node (ref "ACS714-M5") (pin "1") (pinfunction "IP+_1") (pintype "bidirectional"))
      (node (ref "ACS714-M6") (pin "1") (pinfunction "IP+_1") (pintype "bidirectional"))
      (node (ref "ACS714-M7") (pin "1") (pinfunction "IP+_1") (pintype "bidirectional"))
      (node (ref "ACS714-M8") (pin "1") (pinfunction "IP+_1") (pintype "bidirectional"))
      (node (ref "BATT-POS") (pin "P$1") (pinfunction "P$1_P$1") (pintype "bidirectional"))
      (node (ref "BB-8-5V") (pin "1") (pinfunction "VI_1") (pintype "bidirectional"))
      (node (ref "C1") (pin "+") (pinfunction "+_+") (pintype "passive"))
      (node (ref "C18") (pin "1") (pinfunction "1_1") (pintype "passive"))
      (node (ref "C2") (pin "+") (pinfunction "+_+") (pintype "passive"))
      (node (ref "C21") (pin "1") (pinfunction "1_1") (pintype "passive"))
      (node (ref "C22") (pin "1") (pinfunction "1_1") (pintype "passive"))
      (node (ref "C3") (pin "+") (pinfunction "+_+") (pintype "passive"))
      (node (ref "C4") (pin "+") (pinfunction "+_+") (pintype "passive"))
      (node (ref "D1") (pin "C") (pinfunction "C_C") (pintype "passive"))
      (node (ref "D2") (pin "C") (pinfunction "C_C") (pintype "passive"))
      (node (ref "FINN-12V") (pin "1") (pinfunction "+VIN_1") (pintype "bidirectional"))
      (node (ref "POE-12V") (pin "1") (pinfunction "+VIN_1") (pintype "bidirectional"))
      (node (ref "R3") (pin "2") (pinfunction "2_2") (pintype "passive"))
      (node (ref "REY-5V") (pin "P$3") (pinfunction "+VIN_P$3") (pintype "bidirectional"))
    )
    (net (code "92") (name "unconnected-(LT1910-M1-FAULT-Pad3)") (class "Default")
      (node (ref "LT1910-M1") (pin "3") (pinfunction "FAULT_3") (pintype "bidirectional"))
    )
    (net (code "93") (name "unconnected-(LT1910-M1-TIMER-Pad2)") (class "Default")
      (node (ref "LT1910-M1") (pin "2") (pinfunction "TIMER_2") (pintype "bidirectional"))
    )
    (net (code "94") (name "unconnected-(LT1910-M2-FAULT-Pad3)") (class "Default")
      (node (ref "LT1910-M2") (pin "3") (pinfunction "FAULT_3") (pintype "bidirectional"))
    )
    (net (code "95") (name "unconnected-(LT1910-M2-TIMER-Pad2)") (class "Default")
      (node (ref "LT1910-M2") (pin "2") (pinfunction "TIMER_2") (pintype "bidirectional"))
    )
    (net (code "96") (name "unconnected-(LT1910-M3-FAULT-Pad3)") (class "Default")
      (node (ref "LT1910-M3") (pin "3") (pinfunction "FAULT_3") (pintype "bidirectional"))
    )
    (net (code "97") (name "unconnected-(LT1910-M3-TIMER-Pad2)") (class "Default")
      (node (ref "LT1910-M3") (pin "2") (pinfunction "TIMER_2") (pintype "bidirectional"))
    )
    (net (code "98") (name "unconnected-(LT1910-M4-FAULT-Pad3)") (class "Default")
      (node (ref "LT1910-M4") (pin "3") (pinfunction "FAULT_3") (pintype "bidirectional"))
    )
    (net (code "99") (name "unconnected-(LT1910-M4-TIMER-Pad2)") (class "Default")
      (node (ref "LT1910-M4") (pin "2") (pinfunction "TIMER_2") (pintype "bidirectional"))
    )
    (net (code "100") (name "unconnected-(LT1910-M5-FAULT-Pad3)") (class "Default")
      (node (ref "LT1910-M5") (pin "3") (pinfunction "FAULT_3") (pintype "bidirectional"))
    )
    (net (code "101") (name "unconnected-(LT1910-M5-TIMER-Pad2)") (class "Default")
      (node (ref "LT1910-M5") (pin "2") (pinfunction "TIMER_2") (pintype "bidirectional"))
    )
    (net (code "102") (name "unconnected-(LT1910-M6-FAULT-Pad3)") (class "Default")
      (node (ref "LT1910-M6") (pin "3") (pinfunction "FAULT_3") (pintype "bidirectional"))
    )
    (net (code "103") (name "unconnected-(LT1910-M6-TIMER-Pad2)") (class "Default")
      (node (ref "LT1910-M6") (pin "2") (pinfunction "TIMER_2") (pintype "bidirectional"))
    )
    (net (code "104") (name "unconnected-(LT1910-M7-FAULT-Pad3)") (class "Default")
      (node (ref "LT1910-M7") (pin "3") (pinfunction "FAULT_3") (pintype "bidirectional"))
    )
    (net (code "105") (name "unconnected-(LT1910-M7-TIMER-Pad2)") (class "Default")
      (node (ref "LT1910-M7") (pin "2") (pinfunction "TIMER_2") (pintype "bidirectional"))
    )
    (net (code "106") (name "unconnected-(LT1910-M8-FAULT-Pad3)") (class "Default")
      (node (ref "LT1910-M8") (pin "3") (pinfunction "FAULT_3") (pintype "bidirectional"))
    )
    (net (code "107") (name "unconnected-(LT1910-M8-TIMER-Pad2)") (class "Default")
      (node (ref "LT1910-M8") (pin "2") (pinfunction "TIMER_2") (pintype "bidirectional"))
    )
    (net (code "108") (name "unconnected-(REY-5V-TRIM-PadP$4)") (class "Default")
      (node (ref "REY-5V") (pin "P$4") (pinfunction "TRIM_P$4") (pintype "bidirectional"))
    )
    (net (code "109") (name "unconnected-(U$1-PadPA4)") (class "Default")
      (node (ref "U$1") (pin "PA4") (pinfunction "PA4_PA4") (pintype "bidirectional"))
    )
    (net (code "110") (name "unconnected-(U$1-PadPA5)") (class "Default")
      (node (ref "U$1") (pin "PA5") (pinfunction "PA5_PA5") (pintype "bidirectional"))
    )
    (net (code "111") (name "unconnected-(U$1-PadPA6)") (class "Default")
      (node (ref "U$1") (pin "PA6") (pinfunction "PA6_PA6") (pintype "bidirectional"))
    )
    (net (code "112") (name "unconnected-(U$1-PadPB2)") (class "Default")
      (node (ref "U$1") (pin "PB2") (pinfunction "PB2_PB2") (pintype "bidirectional"))
    )
    (net (code "113") (name "unconnected-(U$1-PadPB3)") (class "Default")
      (node (ref "U$1") (pin "PB3") (pinfunction "PB3_PB3") (pintype "bidirectional"))
    )
    (net (code "114") (name "unconnected-(U$1-PadPC6)") (class "Default")
      (node (ref "U$1") (pin "PC6") (pinfunction "PC6_PC6") (pintype "bidirectional"))
    )
    (net (code "115") (name "unconnected-(U$1-PadPC7)") (class "Default")
      (node (ref "U$1") (pin "PC7") (pinfunction "PC7_PC7") (pintype "bidirectional"))
    )
    (net (code "116") (name "unconnected-(U$1-PadPD0)") (class "Default")
      (node (ref "U$1") (pin "PD0") (pinfunction "PD0_PD0") (pintype "bidirectional"))
    )
    (net (code "117") (name "unconnected-(U$1-PadPD1)") (class "Default")
      (node (ref "U$1") (pin "PD1") (pinfunction "PD1_PD1") (pintype "bidirectional"))
    )
    (net (code "118") (name "unconnected-(U$1-PadPD3)") (class "Default")
      (node (ref "U$1") (pin "PD3") (pinfunction "PD3_PD3") (pintype "bidirectional"))
    )
    (net (code "119") (name "unconnected-(U$1-PadPD5)") (class "Default")
      (node (ref "U$1") (pin "PD5") (pinfunction "PD5_PD5") (pintype "bidirectional"))
    )
    (net (code "120") (name "unconnected-(U$1-PadPE0)") (class "Default")
      (node (ref "U$1") (pin "PE0") (pinfunction "PE0_PE0") (pintype "bidirectional"))
    )
    (net (code "121") (name "unconnected-(U$1-PadPE1)") (class "Default")
      (node (ref "U$1") (pin "PE1") (pinfunction "PE1_PE1") (pintype "bidirectional"))
    )
    (net (code "122") (name "unconnected-(U$1-PadPE4)") (class "Default")
      (node (ref "U$1") (pin "PE4") (pinfunction "PE4_PE4") (pintype "bidirectional"))
    )
    (net (code "123") (name "unconnected-(U$1-PadPE5)") (class "Default")
      (node (ref "U$1") (pin "PE5") (pinfunction "PE5_PE5") (pintype "bidirectional"))
    )
    (net (code "124") (name "unconnected-(U$1-PadPF1)") (class "Default")
      (node (ref "U$1") (pin "PF1") (pinfunction "PF1_PF1") (pintype "bidirectional"))
    )
    (net (code "125") (name "unconnected-(U$1-PadPF2)") (class "Default")
      (node (ref "U$1") (pin "PF2") (pinfunction "PF2_PF2") (pintype "bidirectional"))
    )
    (net (code "126") (name "unconnected-(U$1-PadPF3)") (class "Default")
      (node (ref "U$1") (pin "PF3") (pinfunction "PF3_PF3") (pintype "bidirectional"))
    )
    (net (code "127") (name "unconnected-(U$1-PadPG0)") (class "Default")
      (node (ref "U$1") (pin "PG0") (pinfunction "PG0_PG0") (pintype "bidirectional"))
    )
    (net (code "128") (name "unconnected-(U$1-PadPG1)") (class "Default")
      (node (ref "U$1") (pin "PG1") (pinfunction "PG1_PG1") (pintype "bidirectional"))
    )
    (net (code "129") (name "unconnected-(U$1-PadPH2)") (class "Default")
      (node (ref "U$1") (pin "PH2") (pinfunction "PH2_PH2") (pintype "bidirectional"))
    )
    (net (code "130") (name "unconnected-(U$1-PadPH3)") (class "Default")
      (node (ref "U$1") (pin "PH3") (pinfunction "PH3_PH3") (pintype "bidirectional"))
    )
    (net (code "131") (name "unconnected-(U$1-PadPK4)") (class "Default")
      (node (ref "U$1") (pin "PK4") (pinfunction "PK4_PK4") (pintype "bidirectional"))
    )
    (net (code "132") (name "unconnected-(U$1-PadPK5)") (class "Default")
      (node (ref "U$1") (pin "PK5") (pinfunction "PK5_PK5") (pintype "bidirectional"))
    )
    (net (code "133") (name "unconnected-(U$1-PadPL0)") (class "Default")
      (node (ref "U$1") (pin "PL0") (pinfunction "PL0_PL0") (pintype "bidirectional"))
    )
    (net (code "134") (name "unconnected-(U$1-PadPL1)") (class "Default")
      (node (ref "U$1") (pin "PL1") (pinfunction "PL1_PL1") (pintype "bidirectional"))
    )
    (net (code "135") (name "unconnected-(U$1-PadPL2)") (class "Default")
      (node (ref "U$1") (pin "PL2") (pinfunction "PL2_PL2") (pintype "bidirectional"))
    )
    (net (code "136") (name "unconnected-(U$1-PadPL3)") (class "Default")
      (node (ref "U$1") (pin "PL3") (pinfunction "PL3_PL3") (pintype "bidirectional"))
    )
    (net (code "137") (name "unconnected-(U$1-PadPL4)") (class "Default")
      (node (ref "U$1") (pin "PL4") (pinfunction "PL4_PL4") (pintype "bidirectional"))
    )
    (net (code "138") (name "unconnected-(U$1-PadPL5)") (class "Default")
      (node (ref "U$1") (pin "PL5") (pinfunction "PL5_PL5") (pintype "bidirectional"))
    )
    (net (code "139") (name "unconnected-(U$1-PadPM0)") (class "Default")
      (node (ref "U$1") (pin "PM0") (pinfunction "PM0_PM0") (pintype "bidirectional"))
    )
    (net (code "140") (name "unconnected-(U$1-PadPM1)") (class "Default")
      (node (ref "U$1") (pin "PM1") (pinfunction "PM1_PM1") (pintype "bidirectional"))
    )
    (net (code "141") (name "unconnected-(U$1-PadPM2)") (class "Default")
      (node (ref "U$1") (pin "PM2") (pinfunction "PM2_PM2") (pintype "bidirectional"))
    )
    (net (code "142") (name "unconnected-(U$1-PadPM3)") (class "Default")
      (node (ref "U$1") (pin "PM3") (pinfunction "PM3_PM3") (pintype "bidirectional"))
    )
    (net (code "143") (name "unconnected-(U$1-PadPM4)") (class "Default")
      (node (ref "U$1") (pin "PM4") (pinfunction "PM4_PM4") (pintype "bidirectional"))
    )
    (net (code "144") (name "unconnected-(U$1-PadPM5)") (class "Default")
      (node (ref "U$1") (pin "PM5") (pinfunction "PM5_PM5") (pintype "bidirectional"))
    )
    (net (code "145") (name "unconnected-(U$1-PadPM6)") (class "Default")
      (node (ref "U$1") (pin "PM6") (pinfunction "PM6_PM6") (pintype "bidirectional"))
    )
    (net (code "146") (name "unconnected-(U$1-PadPM7)") (class "Default")
      (node (ref "U$1") (pin "PM7") (pinfunction "PM7_PM7") (pintype "bidirectional"))
    )
    (net (code "147") (name "unconnected-(U$1-PadPN2)") (class "Default")
      (node (ref "U$1") (pin "PN2") (pinfunction "PN2_PN2") (pintype "bidirectional"))
    )
    (net (code "148") (name "unconnected-(U$1-PadPN4)") (class "Default")
      (node (ref "U$1") (pin "PN4") (pinfunction "PN4_PN4") (pintype "bidirectional"))
    )
    (net (code "149") (name "unconnected-(U$1-PadPN5)") (class "Default")
      (node (ref "U$1") (pin "PN5") (pinfunction "PN5_PN5") (pintype "bidirectional"))
    )
    (net (code "150") (name "unconnected-(U$1-PadPP4)") (class "Default")
      (node (ref "U$1") (pin "PP4") (pinfunction "PP4_PP4") (pintype "bidirectional"))
    )
    (net (code "151") (name "unconnected-(U$1-PadPQ0)") (class "Default")
      (node (ref "U$1") (pin "PQ0") (pinfunction "PQ0_PQ0") (pintype "bidirectional"))
    )
    (net (code "152") (name "unconnected-(U$1-PadPQ2{slash}PA3)") (class "Default")
      (node (ref "U$1") (pin "PQ2/PA3") (pinfunction "PQ2/PA3_PQ2/PA3") (pintype "bidirectional"))
    )
    (net (code "153") (name "unconnected-(U$1-PadPQ3{slash}PA2)") (class "Default")
      (node (ref "U$1") (pin "PQ3/PA2") (pinfunction "PQ3/PA2_PQ3/PA2") (pintype "bidirectional"))
    )
    (net (code "154") (name "unconnected-(U$5-Pad4)") (class "Default")
      (node (ref "U$5") (pin "4") (pinfunction "4_4") (pintype "bidirectional"))
    )
    (net (code "155") (name "unconnected-(U$5-Pad5)") (class "Default")
      (node (ref "U$5") (pin "5") (pinfunction "5_5") (pintype "bidirectional"))
    )
    (net (code "156") (name "unconnected-(U$6-Pad4)") (class "Default")
      (node (ref "U$6") (pin "4") (pinfunction "4_4") (pintype "bidirectional"))
    )
    (net (code "157") (name "unconnected-(U$6-Pad5)") (class "Default")
      (node (ref "U$6") (pin "5") (pinfunction "5_5") (pintype "bidirectional"))
    )
  )
)
